# RK05ex.net
KiCad netlist of a schematic drawn in EAGLE
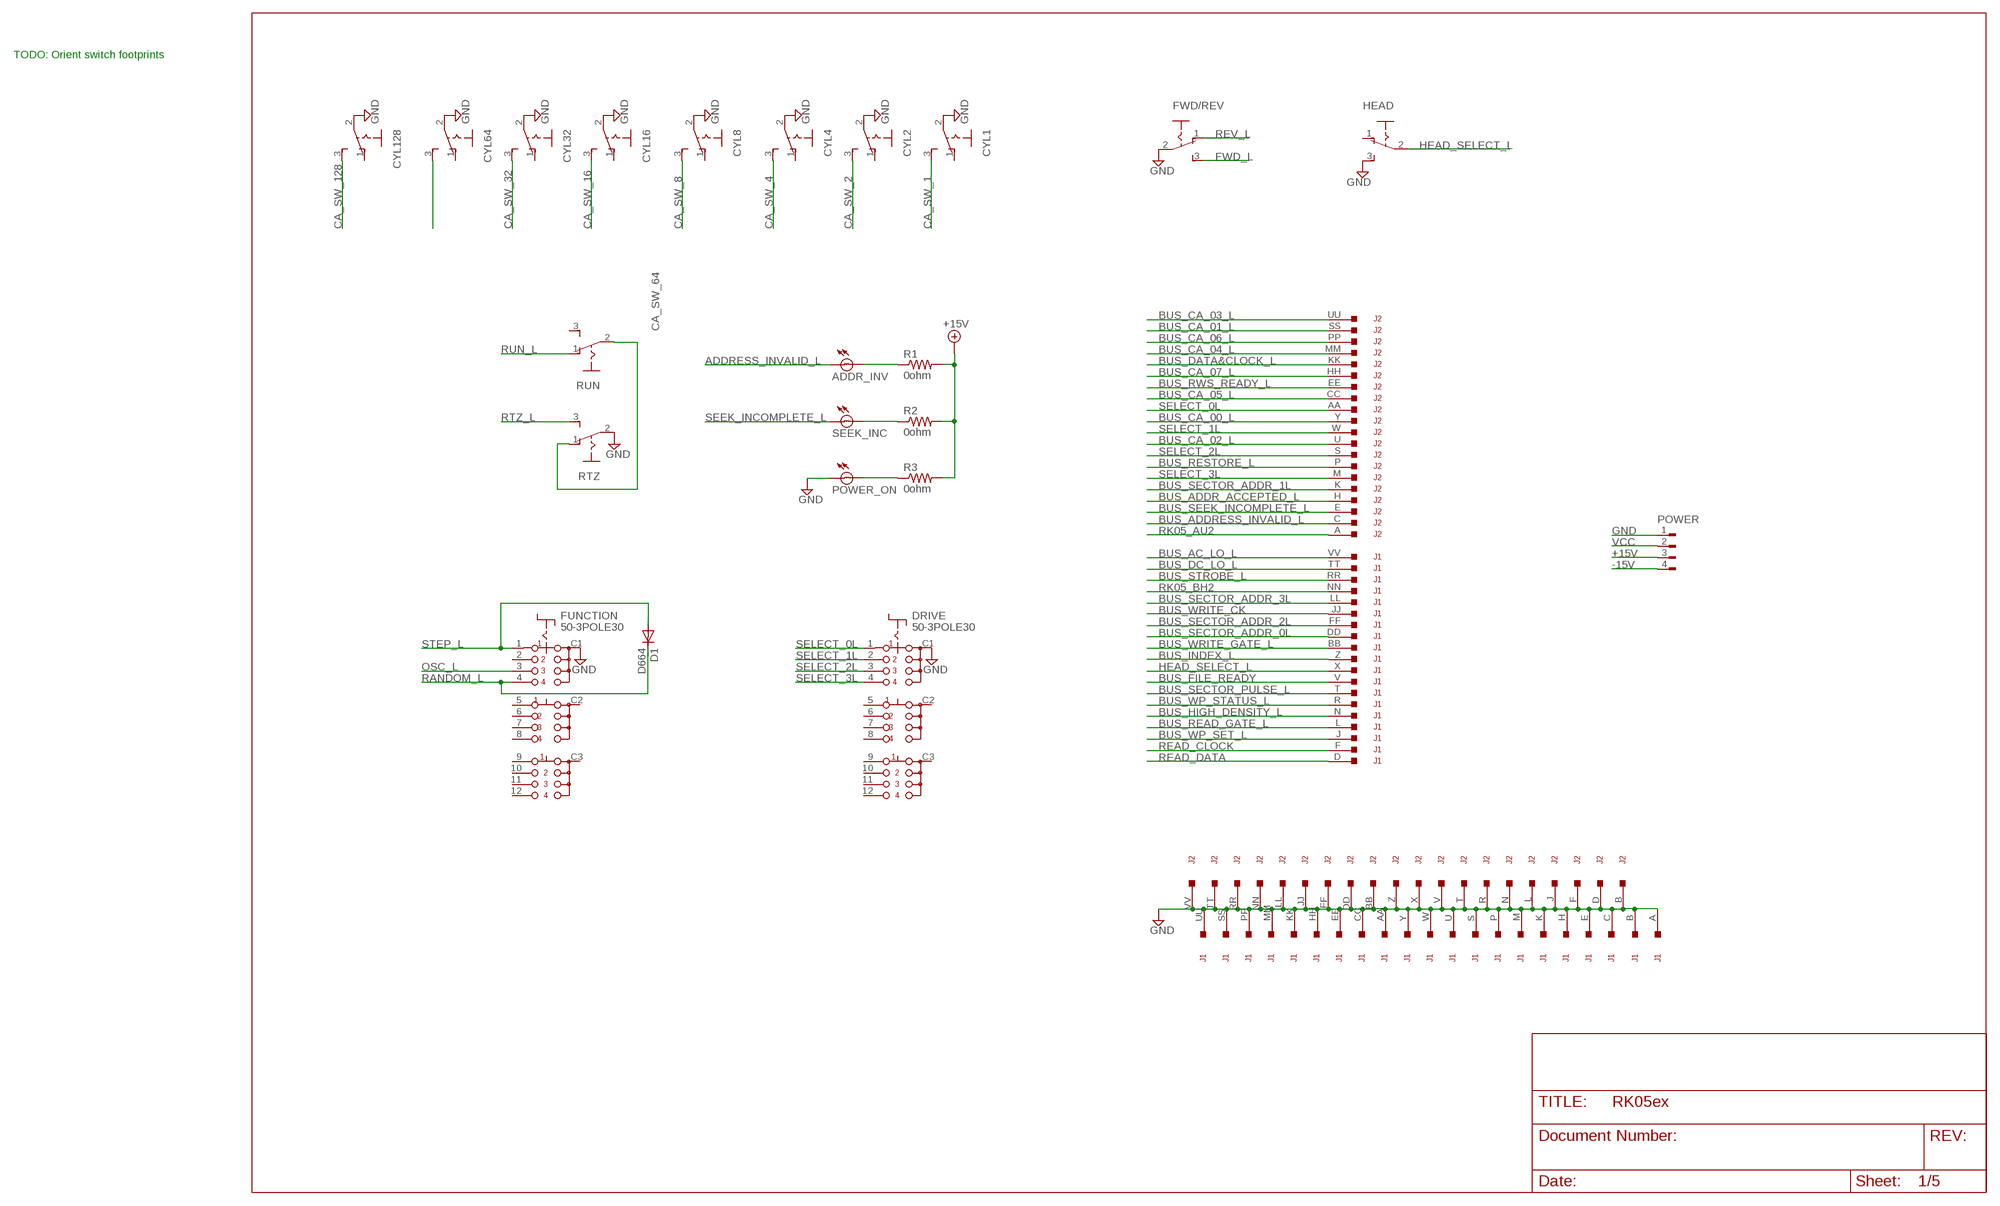
[diagram p0: schematic, sheet 1]
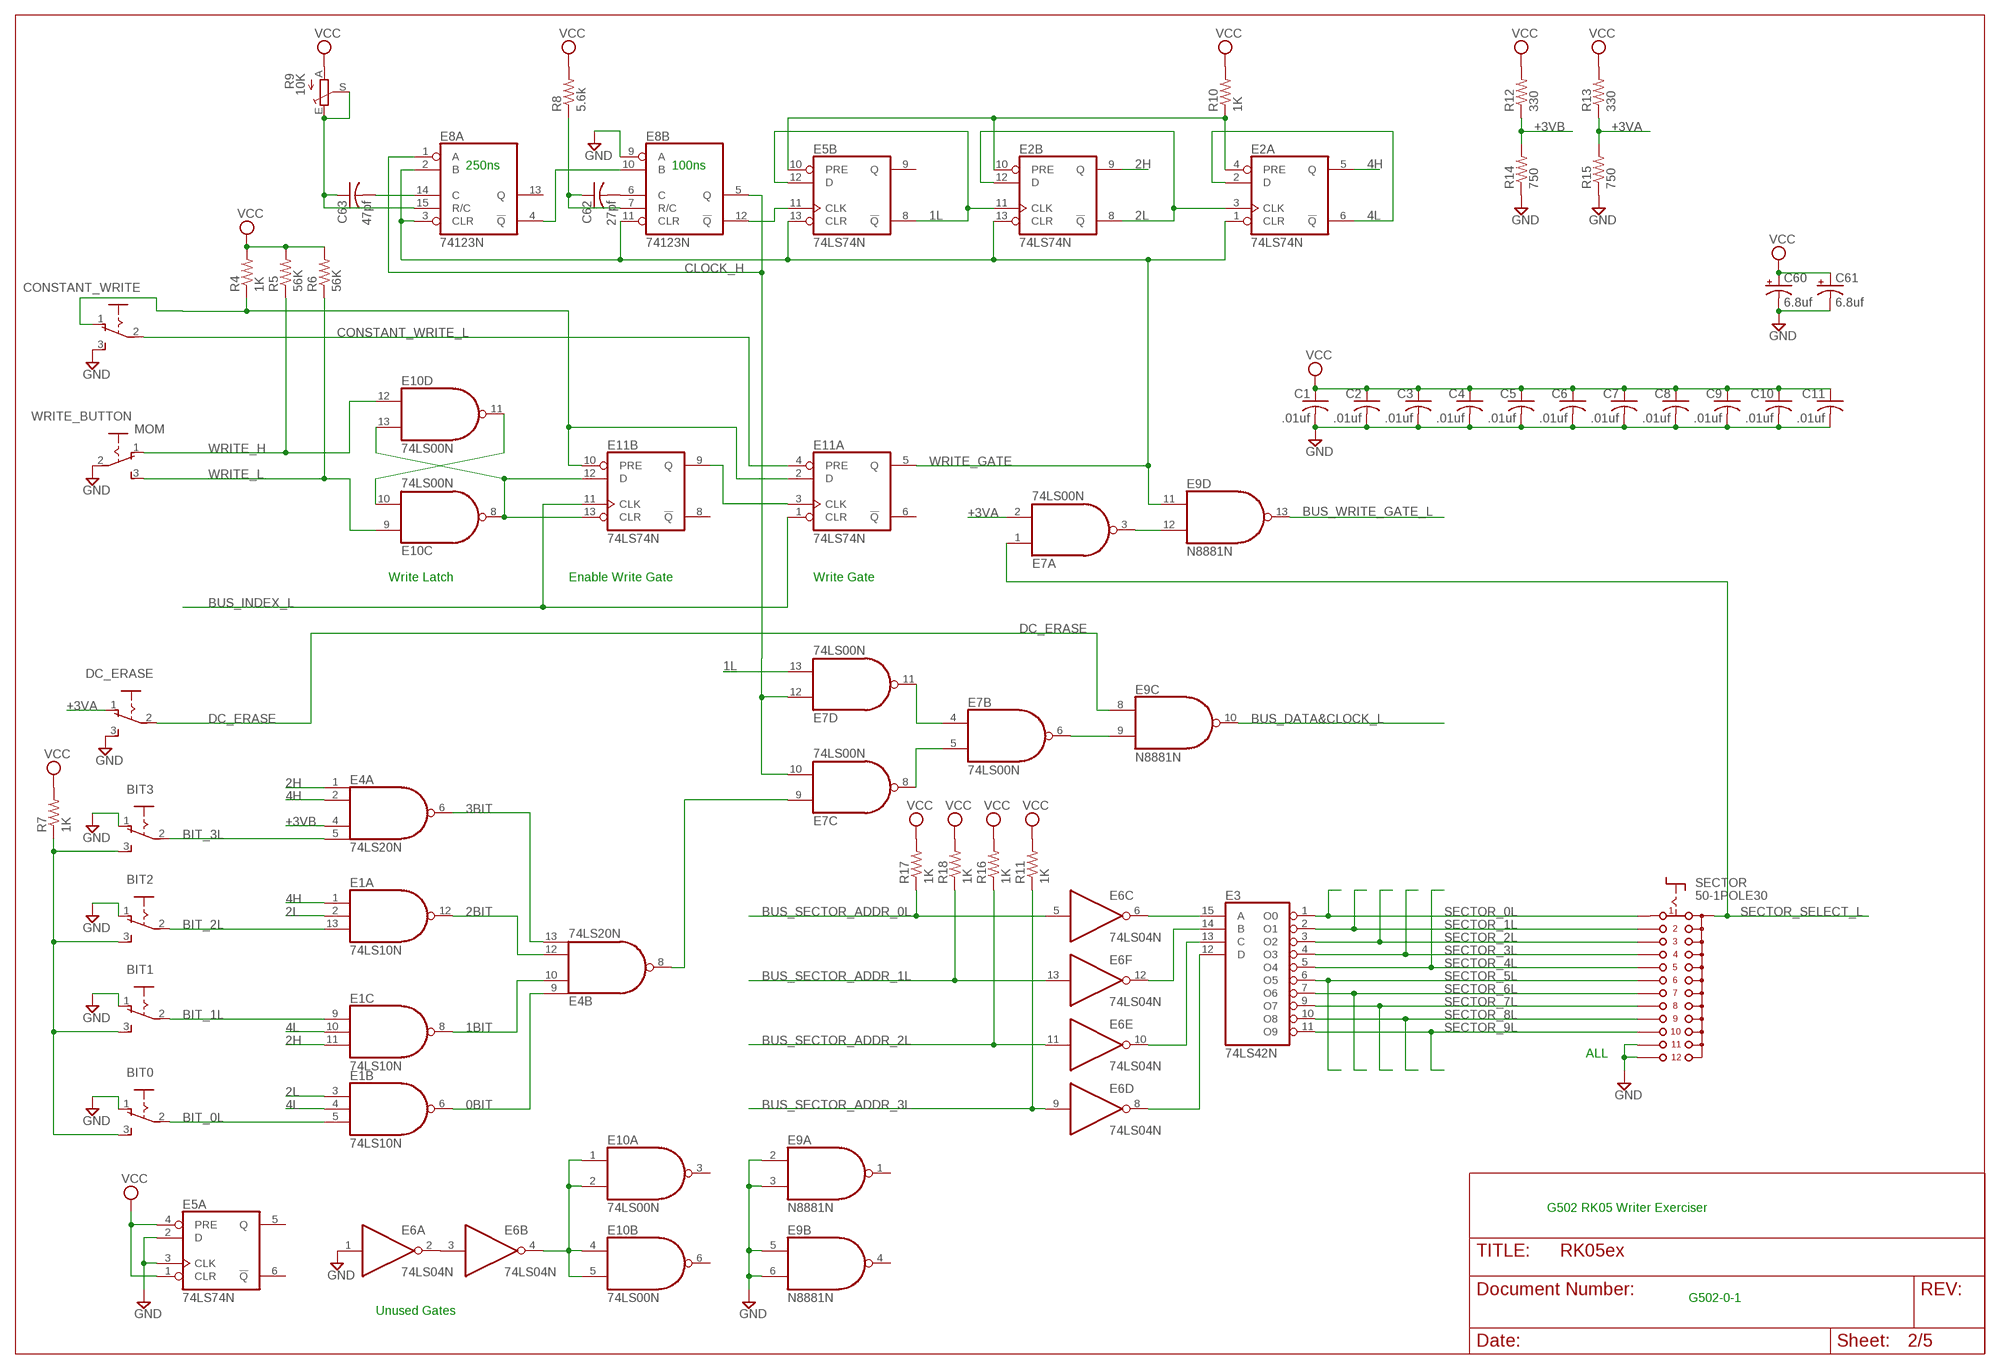
[diagram p1: schematic, sheet 2]
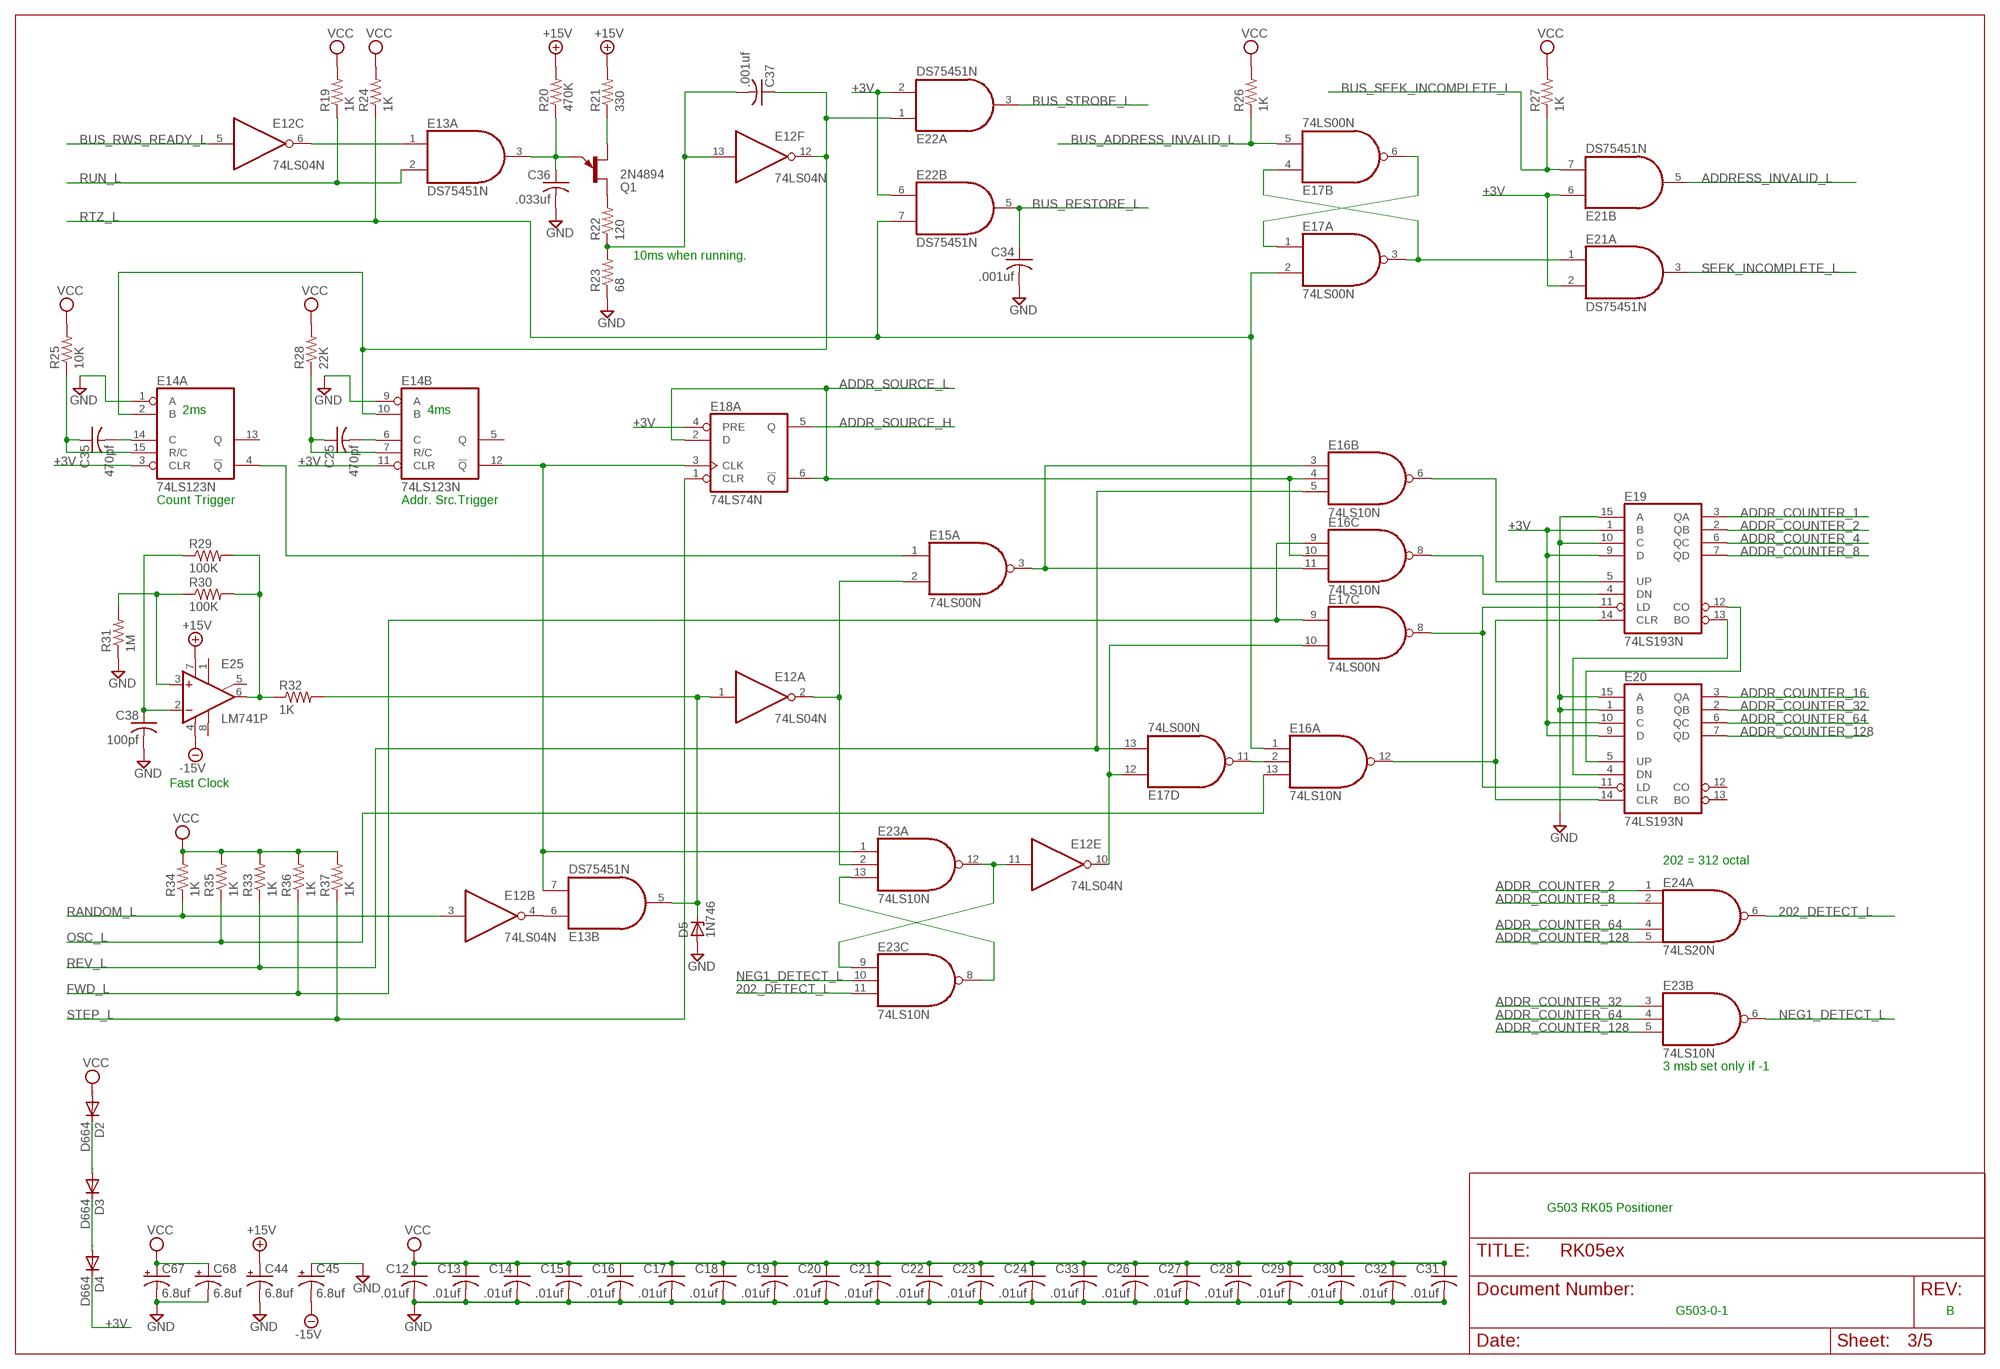
[diagram p2: schematic, sheet 3]
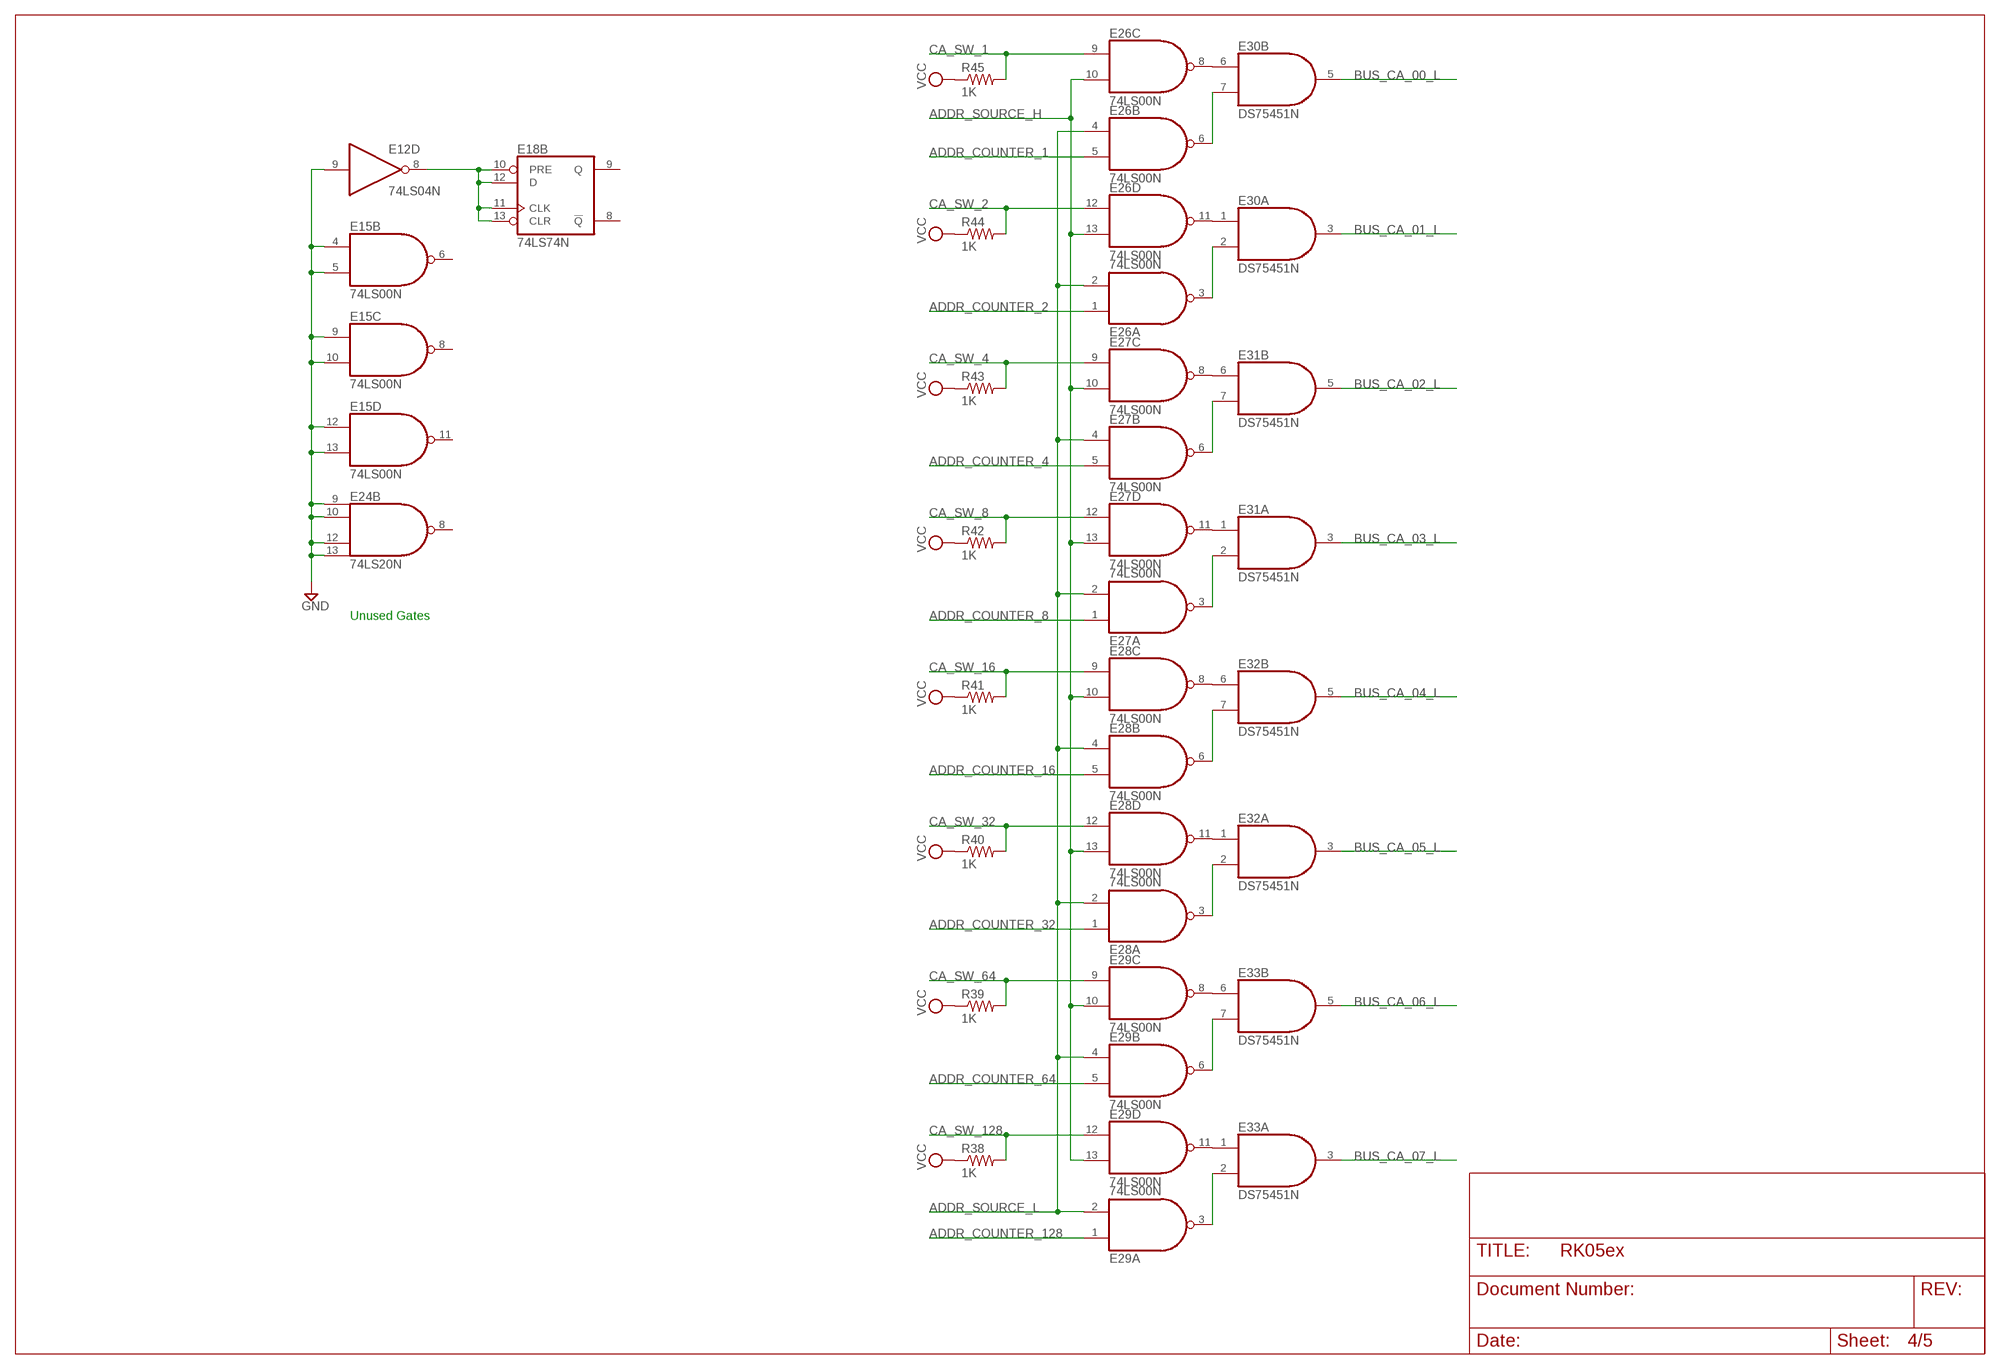
[diagram p3: schematic, sheet 4]
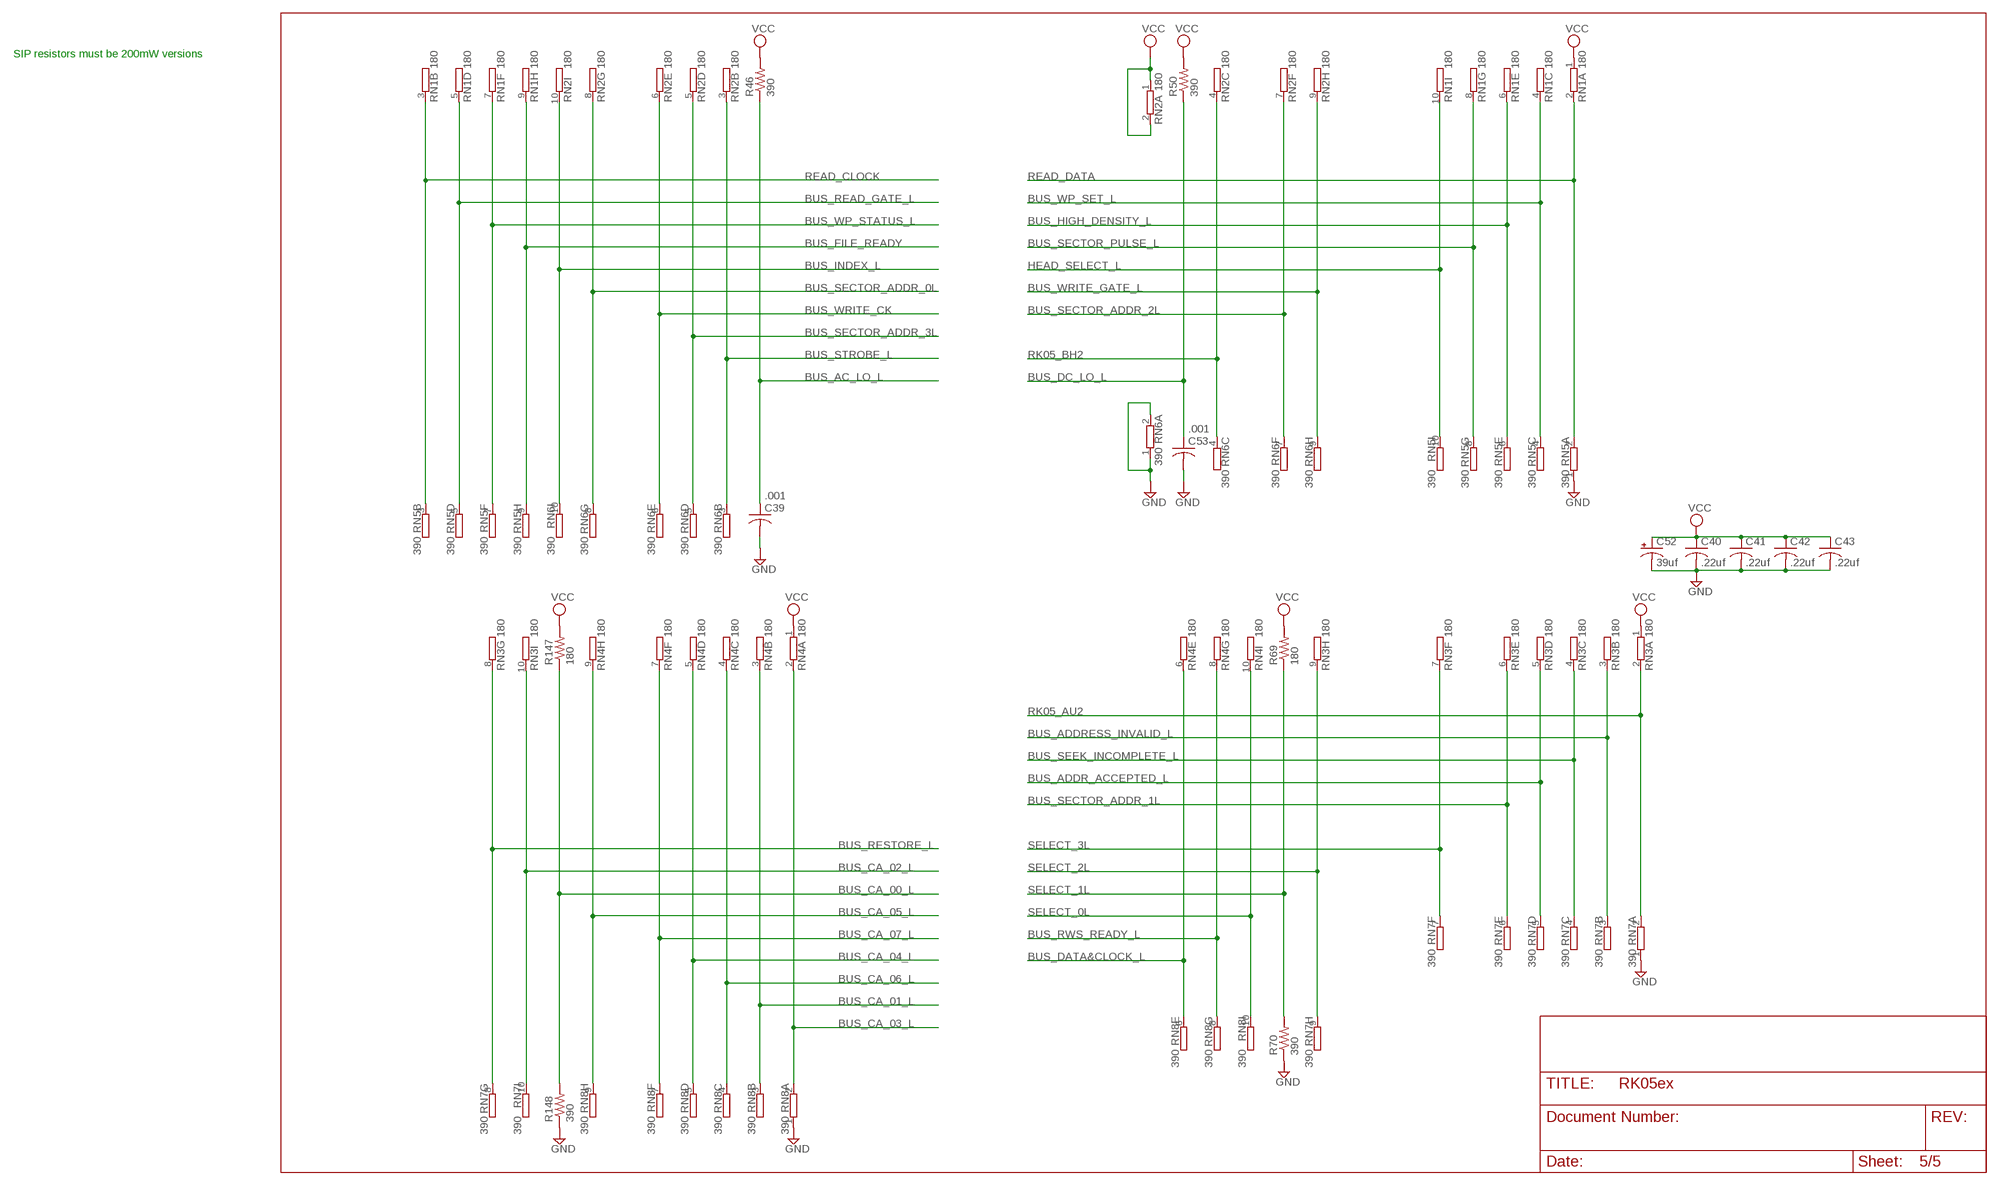
[diagram p4: schematic, sheet 5]

(export (version "E")
  (design (tool "Eeschema 10.0.6"))
  (components
    (comp (ref "C12")
      (value ".01uf")
      (footprint "eagle-import:C075-032X103")
      (libsource (lib "eagle-import") (part "C-US075-032X103"))
    )
    (comp (ref "C13")
      (value ".01uf")
      (footprint "eagle-import:C075-032X103")
      (libsource (lib "eagle-import") (part "C-US075-032X103"))
    )
    (comp (ref "C14")
      (value ".01uf")
      (footprint "eagle-import:C075-032X103")
      (libsource (lib "eagle-import") (part "C-US075-032X103"))
    )
    (comp (ref "C15")
      (value ".01uf")
      (footprint "eagle-import:C075-032X103")
      (libsource (lib "eagle-import") (part "C-US075-032X103"))
    )
    (comp (ref "C16")
      (value ".01uf")
      (footprint "eagle-import:C075-032X103")
      (libsource (lib "eagle-import") (part "C-US075-032X103"))
    )
    (comp (ref "C17")
      (value ".01uf")
      (footprint "eagle-import:C075-032X103")
      (libsource (lib "eagle-import") (part "C-US075-032X103"))
    )
    (comp (ref "C18")
      (value ".01uf")
      (footprint "eagle-import:C075-032X103")
      (libsource (lib "eagle-import") (part "C-US075-032X103"))
    )
    (comp (ref "C19")
      (value ".01uf")
      (footprint "eagle-import:C075-032X103")
      (libsource (lib "eagle-import") (part "C-US075-032X103"))
    )
    (comp (ref "C20")
      (value ".01uf")
      (footprint "eagle-import:C075-032X103")
      (libsource (lib "eagle-import") (part "C-US075-032X103"))
    )
    (comp (ref "C21")
      (value ".01uf")
      (footprint "eagle-import:C075-032X103")
      (libsource (lib "eagle-import") (part "C-US075-032X103"))
    )
    (comp (ref "C22")
      (value ".01uf")
      (footprint "eagle-import:C075-032X103")
      (libsource (lib "eagle-import") (part "C-US075-032X103"))
    )
    (comp (ref "C23")
      (value ".01uf")
      (footprint "eagle-import:C075-032X103")
      (libsource (lib "eagle-import") (part "C-US075-032X103"))
    )
    (comp (ref "C24")
      (value ".01uf")
      (footprint "eagle-import:C075-032X103")
      (libsource (lib "eagle-import") (part "C-US075-032X103"))
    )
    (comp (ref "C25")
      (value "470pf")
      (footprint "eagle-import:C075-032X103")
      (libsource (lib "eagle-import") (part "C-US075-032X103"))
    )
    (comp (ref "C26")
      (value ".01uf")
      (footprint "eagle-import:C075-032X103")
      (libsource (lib "eagle-import") (part "C-US075-032X103"))
    )
    (comp (ref "C27")
      (value ".01uf")
      (footprint "eagle-import:C075-032X103")
      (libsource (lib "eagle-import") (part "C-US075-032X103"))
    )
    (comp (ref "C28")
      (value ".01uf")
      (footprint "eagle-import:C075-032X103")
      (libsource (lib "eagle-import") (part "C-US075-032X103"))
    )
    (comp (ref "C29")
      (value ".01uf")
      (footprint "eagle-import:C075-032X103")
      (libsource (lib "eagle-import") (part "C-US075-032X103"))
    )
    (comp (ref "C30")
      (value ".01uf")
      (footprint "eagle-import:C075-032X103")
      (libsource (lib "eagle-import") (part "C-US075-032X103"))
    )
    (comp (ref "C31")
      (value ".01uf")
      (footprint "eagle-import:C075-032X103")
      (libsource (lib "eagle-import") (part "C-US075-032X103"))
    )
    (comp (ref "C32")
      (value ".01uf")
      (footprint "eagle-import:C075-032X103")
      (libsource (lib "eagle-import") (part "C-US075-032X103"))
    )
    (comp (ref "C33")
      (value ".01uf")
      (footprint "eagle-import:C075-032X103")
      (libsource (lib "eagle-import") (part "C-US075-032X103"))
    )
    (comp (ref "C34")
      (value ".001uf")
      (footprint "eagle-import:C075-032X103")
      (libsource (lib "eagle-import") (part "C-US075-032X103"))
    )
    (comp (ref "C35")
      (value "470pf")
      (footprint "eagle-import:C075-032X103")
      (libsource (lib "eagle-import") (part "C-US075-032X103"))
    )
    (comp (ref "C36")
      (value ".033uf")
      (footprint "eagle-import:C075-032X103")
      (libsource (lib "eagle-import") (part "C-US075-032X103"))
    )
    (comp (ref "C37")
      (value ".001uf")
      (footprint "eagle-import:C075-032X103")
      (libsource (lib "eagle-import") (part "C-US075-032X103"))
    )
    (comp (ref "C38")
      (value "100pf")
      (footprint "eagle-import:C075-032X103")
      (libsource (lib "eagle-import") (part "C-US075-032X103"))
    )
    (comp (ref "C44")
      (value "6.8uf")
      (footprint "eagle-import:E15-5")
      (libsource (lib "eagle-import") (part "CPOL-USE15-5AXIAL"))
    )
    (comp (ref "C45")
      (value "6.8uf")
      (footprint "eagle-import:E15-5")
      (libsource (lib "eagle-import") (part "CPOL-USE15-5AXIAL"))
    )
    (comp (ref "C67")
      (value "6.8uf")
      (footprint "eagle-import:E15-5")
      (libsource (lib "eagle-import") (part "CPOL-USE15-5AXIAL"))
    )
    (comp (ref "C68")
      (value "6.8uf")
      (footprint "eagle-import:E15-5")
      (libsource (lib "eagle-import") (part "CPOL-USE15-5AXIAL"))
    )
    (comp (ref "D2")
      (value "D664")
      (footprint "eagle-import:DO35-10")
      (libsource (lib "eagle-import") (part "1N4148DO35-10"))
    )
    (comp (ref "D3")
      (value "D664")
      (footprint "eagle-import:DO35-10")
      (libsource (lib "eagle-import") (part "1N4148DO35-10"))
    )
    (comp (ref "D4")
      (value "D664")
      (footprint "eagle-import:DO35-10")
      (libsource (lib "eagle-import") (part "1N4148DO35-10"))
    )
    (comp (ref "D5")
      (value "1N746")
      (footprint "eagle-import:DO35Z10")
      (libsource (lib "eagle-import") (part "ZENER-DIODEDO35Z10"))
    )
    (comp (ref "E12")
      (value "74LS04N")
      (footprint "eagle-import:DIL14")
      (libsource (lib "eagle-import") (part "7404NLS"))
    )
    (comp (ref "E13")
      (value "DS75451N")
      (footprint "eagle-import:DIL08")
      (libsource (lib "eagle-import") (part "DS75451N"))
    )
    (comp (ref "E14")
      (value "74LS123N")
      (footprint "eagle-import:DIL16")
      (libsource (lib "eagle-import") (part "74123NLS"))
    )
    (comp (ref "E15")
      (value "74LS00N")
      (footprint "eagle-import:DIL14")
      (libsource (lib "eagle-import") (part "7400NLS"))
    )
    (comp (ref "E16")
      (value "74LS10N")
      (footprint "eagle-import:DIL14")
      (libsource (lib "eagle-import") (part "7410NAS"))
    )
    (comp (ref "E17")
      (value "74LS00N")
      (footprint "eagle-import:DIL14")
      (libsource (lib "eagle-import") (part "7400NLS"))
    )
    (comp (ref "E18")
      (value "74LS74N")
      (footprint "eagle-import:DIL14")
      (libsource (lib "eagle-import") (part "7474NLS"))
    )
    (comp (ref "E19")
      (value "74LS193N")
      (footprint "eagle-import:DIL16")
      (libsource (lib "eagle-import") (part "74193NLS"))
    )
    (comp (ref "E20")
      (value "74LS193N")
      (footprint "eagle-import:DIL16")
      (libsource (lib "eagle-import") (part "74193NLS"))
    )
    (comp (ref "E21")
      (value "DS75451N")
      (footprint "eagle-import:DIL08")
      (libsource (lib "eagle-import") (part "DS75451N"))
    )
    (comp (ref "E22")
      (value "DS75451N")
      (footprint "eagle-import:DIL08")
      (libsource (lib "eagle-import") (part "DS75451N"))
    )
    (comp (ref "E23")
      (value "74LS10N")
      (footprint "eagle-import:DIL14")
      (libsource (lib "eagle-import") (part "7410NAS"))
    )
    (comp (ref "E24")
      (value "74LS20N")
      (footprint "eagle-import:DIL14")
      (libsource (lib "eagle-import") (part "7420NLS"))
    )
    (comp (ref "E25")
      (value "LM741P")
      (footprint "eagle-import:DIL08")
      (libsource (lib "eagle-import") (part "741PLM"))
    )
    (comp (ref "Q1")
      (value "2N4894")
      (footprint "eagle-import:TO92E")
      (libsource (lib "eagle-import") (part "2N4870"))
    )
    (comp (ref "R19")
      (value "1K")
      (footprint "eagle-import:0207_10")
      (libsource (lib "eagle-import") (part "R-US_0207/10"))
    )
    (comp (ref "R20")
      (value "470K")
      (footprint "eagle-import:0207_10")
      (libsource (lib "eagle-import") (part "R-US_0207/10"))
    )
    (comp (ref "R21")
      (value "330")
      (footprint "eagle-import:0207_10")
      (libsource (lib "eagle-import") (part "R-US_0207/10"))
    )
    (comp (ref "R22")
      (value "120")
      (footprint "eagle-import:0207_10")
      (libsource (lib "eagle-import") (part "R-US_0207/10"))
    )
    (comp (ref "R23")
      (value "68")
      (footprint "eagle-import:0207_10")
      (libsource (lib "eagle-import") (part "R-US_0207/10"))
    )
    (comp (ref "R24")
      (value "1K")
      (footprint "eagle-import:0207_10")
      (libsource (lib "eagle-import") (part "R-US_0207/10"))
    )
    (comp (ref "R25")
      (value "10K")
      (footprint "eagle-import:0207_10")
      (libsource (lib "eagle-import") (part "R-US_0207/10"))
    )
    (comp (ref "R26")
      (value "1K")
      (footprint "eagle-import:0207_10")
      (libsource (lib "eagle-import") (part "R-US_0207/10"))
    )
    (comp (ref "R27")
      (value "1K")
      (footprint "eagle-import:0207_10")
      (libsource (lib "eagle-import") (part "R-US_0207/10"))
    )
    (comp (ref "R28")
      (value "22K")
      (footprint "eagle-import:0207_10")
      (libsource (lib "eagle-import") (part "R-US_0207/10"))
    )
    (comp (ref "R29")
      (value "100K")
      (footprint "eagle-import:0207_10")
      (libsource (lib "eagle-import") (part "R-US_0207/10"))
    )
    (comp (ref "R30")
      (value "100K")
      (footprint "eagle-import:0207_10")
      (libsource (lib "eagle-import") (part "R-US_0207/10"))
    )
    (comp (ref "R31")
      (value "1M")
      (footprint "eagle-import:0207_10")
      (libsource (lib "eagle-import") (part "R-US_0207/10"))
    )
    (comp (ref "R32")
      (value "1K")
      (footprint "eagle-import:0207_10")
      (libsource (lib "eagle-import") (part "R-US_0207/10"))
    )
    (comp (ref "R33")
      (value "1K")
      (footprint "eagle-import:0207_10")
      (libsource (lib "eagle-import") (part "R-US_0207/10"))
    )
    (comp (ref "R34")
      (value "1K")
      (footprint "eagle-import:0207_10")
      (libsource (lib "eagle-import") (part "R-US_0207/10"))
    )
    (comp (ref "R35")
      (value "1K")
      (footprint "eagle-import:0207_10")
      (libsource (lib "eagle-import") (part "R-US_0207/10"))
    )
    (comp (ref "R36")
      (value "1K")
      (footprint "eagle-import:0207_10")
      (libsource (lib "eagle-import") (part "R-US_0207/10"))
    )
    (comp (ref "R37")
      (value "1K")
      (footprint "eagle-import:0207_10")
      (libsource (lib "eagle-import") (part "R-US_0207/10"))
    )
    (comp (ref "E26")
      (value "74LS00N")
      (footprint "eagle-import:DIL14")
      (libsource (lib "eagle-import") (part "7400NLS"))
    )
    (comp (ref "E27")
      (value "74LS00N")
      (footprint "eagle-import:DIL14")
      (libsource (lib "eagle-import") (part "7400NLS"))
    )
    (comp (ref "E28")
      (value "74LS00N")
      (footprint "eagle-import:DIL14")
      (libsource (lib "eagle-import") (part "7400NLS"))
    )
    (comp (ref "E29")
      (value "74LS00N")
      (footprint "eagle-import:DIL14")
      (libsource (lib "eagle-import") (part "7400NLS"))
    )
    (comp (ref "E30")
      (value "DS75451N")
      (footprint "eagle-import:DIL08")
      (libsource (lib "eagle-import") (part "DS75451N"))
    )
    (comp (ref "E31")
      (value "DS75451N")
      (footprint "eagle-import:DIL08")
      (libsource (lib "eagle-import") (part "DS75451N"))
    )
    (comp (ref "E32")
      (value "DS75451N")
      (footprint "eagle-import:DIL08")
      (libsource (lib "eagle-import") (part "DS75451N"))
    )
    (comp (ref "E33")
      (value "DS75451N")
      (footprint "eagle-import:DIL08")
      (libsource (lib "eagle-import") (part "DS75451N"))
    )
    (comp (ref "R38")
      (value "1K")
      (footprint "eagle-import:0207_10")
      (libsource (lib "eagle-import") (part "R-US_0207/10"))
    )
    (comp (ref "R39")
      (value "1K")
      (footprint "eagle-import:0207_10")
      (libsource (lib "eagle-import") (part "R-US_0207/10"))
    )
    (comp (ref "R40")
      (value "1K")
      (footprint "eagle-import:0207_10")
      (libsource (lib "eagle-import") (part "R-US_0207/10"))
    )
    (comp (ref "R41")
      (value "1K")
      (footprint "eagle-import:0207_10")
      (libsource (lib "eagle-import") (part "R-US_0207/10"))
    )
    (comp (ref "R42")
      (value "1K")
      (footprint "eagle-import:0207_10")
      (libsource (lib "eagle-import") (part "R-US_0207/10"))
    )
    (comp (ref "R43")
      (value "1K")
      (footprint "eagle-import:0207_10")
      (libsource (lib "eagle-import") (part "R-US_0207/10"))
    )
    (comp (ref "R44")
      (value "1K")
      (footprint "eagle-import:0207_10")
      (libsource (lib "eagle-import") (part "R-US_0207/10"))
    )
    (comp (ref "R45")
      (value "1K")
      (footprint "eagle-import:0207_10")
      (libsource (lib "eagle-import") (part "R-US_0207/10"))
    )
    (comp (ref "C39")
      (value ".001")
      (footprint "eagle-import:C050-025X075")
      (libsource (lib "eagle-import") (part "C-US050-025X075"))
    )
    (comp (ref "C40")
      (value ".22uf")
      (footprint "eagle-import:C050-025X075")
      (libsource (lib "eagle-import") (part "C-US050-025X075"))
    )
    (comp (ref "C41")
      (value ".22uf")
      (footprint "eagle-import:C050-025X075")
      (libsource (lib "eagle-import") (part "C-US050-025X075"))
    )
    (comp (ref "C42")
      (value ".22uf")
      (footprint "eagle-import:C050-025X075")
      (libsource (lib "eagle-import") (part "C-US050-025X075"))
    )
    (comp (ref "C43")
      (value ".22uf")
      (footprint "eagle-import:C050-025X075")
      (libsource (lib "eagle-import") (part "C-US050-025X075"))
    )
    (comp (ref "C52")
      (value "39uf")
      (footprint "eagle-import:E15-5")
      (libsource (lib "eagle-import") (part "CPOL-USE15-5AXIAL"))
    )
    (comp (ref "C53")
      (value ".001")
      (footprint "eagle-import:C050-025X075")
      (libsource (lib "eagle-import") (part "C-US050-025X075"))
    )
    (comp (ref "R46")
      (value "390")
      (footprint "eagle-import:0207_10")
      (libsource (lib "eagle-import") (part "R-US_0207/10"))
    )
    (comp (ref "R50")
      (value "390")
      (footprint "eagle-import:0207_10")
      (libsource (lib "eagle-import") (part "R-US_0207/10"))
    )
    (comp (ref "R69")
      (value "180")
      (footprint "eagle-import:0207_10")
      (libsource (lib "eagle-import") (part "R-US_0207/10"))
    )
    (comp (ref "R70")
      (value "390")
      (footprint "eagle-import:0207_10")
      (libsource (lib "eagle-import") (part "R-US_0207/10"))
    )
    (comp (ref "R147")
      (value "180")
      (footprint "eagle-import:0207_10")
      (libsource (lib "eagle-import") (part "R-US_0207/10"))
    )
    (comp (ref "R148")
      (value "390")
      (footprint "eagle-import:0207_10")
      (libsource (lib "eagle-import") (part "R-US_0207/10"))
    )
    (comp (ref "RN1")
      (value "180")
      (footprint "eagle-import:SIL10")
      (libsource (lib "eagle-import") (part "GE09R"))
    )
    (comp (ref "RN2")
      (value "180")
      (footprint "eagle-import:SIL10")
      (libsource (lib "eagle-import") (part "GE09R"))
    )
    (comp (ref "RN3")
      (value "180")
      (footprint "eagle-import:SIL10")
      (libsource (lib "eagle-import") (part "GE09R"))
    )
    (comp (ref "RN4")
      (value "180")
      (footprint "eagle-import:SIL10")
      (libsource (lib "eagle-import") (part "GE09R"))
    )
    (comp (ref "RN5")
      (value "390")
      (footprint "eagle-import:SIL10")
      (libsource (lib "eagle-import") (part "GE09R"))
    )
    (comp (ref "RN6")
      (value "390")
      (footprint "eagle-import:SIL10")
      (libsource (lib "eagle-import") (part "GE09R"))
    )
    (comp (ref "RN7")
      (value "390")
      (footprint "eagle-import:SIL10")
      (libsource (lib "eagle-import") (part "GE09R"))
    )
    (comp (ref "RN8")
      (value "390")
      (footprint "eagle-import:SIL10")
      (libsource (lib "eagle-import") (part "GE09R"))
    )
    (comp (ref "BIT0")
      (value "255SB")
      (footprint "eagle-import:255SB")
      (libsource (lib "eagle-import") (part "255SB"))
    )
    (comp (ref "BIT1")
      (value "255SB")
      (footprint "eagle-import:255SB")
      (libsource (lib "eagle-import") (part "255SB"))
    )
    (comp (ref "BIT2")
      (value "255SB")
      (footprint "eagle-import:255SB")
      (libsource (lib "eagle-import") (part "255SB"))
    )
    (comp (ref "BIT3")
      (value "255SB")
      (footprint "eagle-import:255SB")
      (libsource (lib "eagle-import") (part "255SB"))
    )
    (comp (ref "C1")
      (value ".01uf")
      (footprint "eagle-import:C075-032X103")
      (libsource (lib "eagle-import") (part "C-US075-032X103"))
    )
    (comp (ref "C2")
      (value ".01uf")
      (footprint "eagle-import:C075-032X103")
      (libsource (lib "eagle-import") (part "C-US075-032X103"))
    )
    (comp (ref "C3")
      (value ".01uf")
      (footprint "eagle-import:C075-032X103")
      (libsource (lib "eagle-import") (part "C-US075-032X103"))
    )
    (comp (ref "C4")
      (value ".01uf")
      (footprint "eagle-import:C075-032X103")
      (libsource (lib "eagle-import") (part "C-US075-032X103"))
    )
    (comp (ref "C5")
      (value ".01uf")
      (footprint "eagle-import:C075-032X103")
      (libsource (lib "eagle-import") (part "C-US075-032X103"))
    )
    (comp (ref "C6")
      (value ".01uf")
      (footprint "eagle-import:C075-032X103")
      (libsource (lib "eagle-import") (part "C-US075-032X103"))
    )
    (comp (ref "C7")
      (value ".01uf")
      (footprint "eagle-import:C075-032X103")
      (libsource (lib "eagle-import") (part "C-US075-032X103"))
    )
    (comp (ref "C8")
      (value ".01uf")
      (footprint "eagle-import:C075-032X103")
      (libsource (lib "eagle-import") (part "C-US075-032X103"))
    )
    (comp (ref "C9")
      (value ".01uf")
      (footprint "eagle-import:C075-032X103")
      (libsource (lib "eagle-import") (part "C-US075-032X103"))
    )
    (comp (ref "C10")
      (value ".01uf")
      (footprint "eagle-import:C075-032X103")
      (libsource (lib "eagle-import") (part "C-US075-032X103"))
    )
    (comp (ref "C11")
      (value ".01uf")
      (footprint "eagle-import:C075-032X103")
      (libsource (lib "eagle-import") (part "C-US075-032X103"))
    )
    (comp (ref "C60")
      (value "6.8uf")
      (footprint "eagle-import:E15-5")
      (libsource (lib "eagle-import") (part "CPOL-USE15-5AXIAL"))
    )
    (comp (ref "C61")
      (value "6.8uf")
      (footprint "eagle-import:E15-5")
      (libsource (lib "eagle-import") (part "CPOL-USE15-5AXIAL"))
    )
    (comp (ref "C62")
      (value "27pf")
      (footprint "eagle-import:C075-032X103")
      (libsource (lib "eagle-import") (part "C-US075-032X103"))
    )
    (comp (ref "C63")
      (value "47pf")
      (footprint "eagle-import:C075-032X103")
      (libsource (lib "eagle-import") (part "C-US075-032X103"))
    )
    (comp (ref "CONSTANT_WRITE")
      (value "255SB")
      (footprint "eagle-import:255SB")
      (libsource (lib "eagle-import") (part "255SB"))
    )
    (comp (ref "DC_ERASE")
      (value "255SB")
      (footprint "eagle-import:255SB")
      (libsource (lib "eagle-import") (part "255SB"))
    )
    (comp (ref "E1")
      (value "74LS10N")
      (footprint "eagle-import:DIL14")
      (libsource (lib "eagle-import") (part "7410NLS"))
    )
    (comp (ref "E2")
      (value "74LS74N")
      (footprint "eagle-import:DIL14")
      (libsource (lib "eagle-import") (part "7474NLS"))
    )
    (comp (ref "E3")
      (value "74LS42N")
      (footprint "eagle-import:DIL16")
      (libsource (lib "eagle-import") (part "7442NLS"))
    )
    (comp (ref "E4")
      (value "74LS20N")
      (footprint "eagle-import:DIL14")
      (libsource (lib "eagle-import") (part "7420NLS"))
    )
    (comp (ref "E5")
      (value "74LS74N")
      (footprint "eagle-import:DIL14")
      (libsource (lib "eagle-import") (part "7474NLS"))
    )
    (comp (ref "E6")
      (value "74LS04N")
      (footprint "eagle-import:DIL14")
      (libsource (lib "eagle-import") (part "7404NLS"))
    )
    (comp (ref "E7")
      (value "74LS00N")
      (footprint "eagle-import:DIL14")
      (libsource (lib "eagle-import") (part "7400NLS"))
    )
    (comp (ref "E8")
      (value "74123N")
      (footprint "eagle-import:DIL16")
      (libsource (lib "eagle-import") (part "74123NLS"))
    )
    (comp (ref "E9")
      (value "N8881N")
      (footprint "eagle-import:DIL14")
      (libsource (lib "eagle-import") (part "N8881N"))
    )
    (comp (ref "E10")
      (value "74LS00N")
      (footprint "eagle-import:DIL14")
      (libsource (lib "eagle-import") (part "7400NLS"))
    )
    (comp (ref "E11")
      (value "74LS74N")
      (footprint "eagle-import:DIL14")
      (libsource (lib "eagle-import") (part "7474NLS"))
    )
    (comp (ref "R4")
      (value "1K")
      (footprint "eagle-import:0207_10")
      (libsource (lib "eagle-import") (part "R-US_0207/10"))
    )
    (comp (ref "R5")
      (value "56K")
      (footprint "eagle-import:0207_10")
      (libsource (lib "eagle-import") (part "R-US_0207/10"))
    )
    (comp (ref "R6")
      (value "56K")
      (footprint "eagle-import:0207_10")
      (libsource (lib "eagle-import") (part "R-US_0207/10"))
    )
    (comp (ref "R7")
      (value "1K")
      (footprint "eagle-import:0207_10")
      (libsource (lib "eagle-import") (part "R-US_0207/10"))
    )
    (comp (ref "R8")
      (value "5.6k")
      (footprint "eagle-import:0207_10")
      (libsource (lib "eagle-import") (part "R-US_0207/10"))
    )
    (comp (ref "R9")
      (value "10K")
      (footprint "eagle-import:SP19L")
      (libsource (lib "eagle-import") (part "TRIM_EU-B90P"))
    )
    (comp (ref "R10")
      (value "1K")
      (footprint "eagle-import:0207_10")
      (libsource (lib "eagle-import") (part "R-US_0207/10"))
    )
    (comp (ref "R11")
      (value "1K")
      (footprint "eagle-import:0207_10")
      (libsource (lib "eagle-import") (part "R-US_0207/10"))
    )
    (comp (ref "R12")
      (value "330")
      (footprint "eagle-import:0207_10")
      (libsource (lib "eagle-import") (part "R-US_0207/10"))
    )
    (comp (ref "R13")
      (value "330")
      (footprint "eagle-import:0207_10")
      (libsource (lib "eagle-import") (part "R-US_0207/10"))
    )
    (comp (ref "R14")
      (value "750")
      (footprint "eagle-import:0207_10")
      (libsource (lib "eagle-import") (part "R-US_0207/10"))
    )
    (comp (ref "R15")
      (value "750")
      (footprint "eagle-import:0207_10")
      (libsource (lib "eagle-import") (part "R-US_0207/10"))
    )
    (comp (ref "R16")
      (value "1K")
      (footprint "eagle-import:0207_10")
      (libsource (lib "eagle-import") (part "R-US_0207/10"))
    )
    (comp (ref "R17")
      (value "1K")
      (footprint "eagle-import:0207_10")
      (libsource (lib "eagle-import") (part "R-US_0207/10"))
    )
    (comp (ref "R18")
      (value "1K")
      (footprint "eagle-import:0207_10")
      (libsource (lib "eagle-import") (part "R-US_0207/10"))
    )
    (comp (ref "SECTOR")
      (value "50-1POLE30")
      (footprint "eagle-import:50-1POLE30")
      (libsource (lib "eagle-import") (part "50-1POLE30"))
    )
    (comp (ref "WRITE_BUTTON")
      (value "MOM")
      (footprint "eagle-import:255SB")
      (libsource (lib "eagle-import") (part "255SB"))
    )
    (comp (ref "ADDR_INV")
      (value "BULB")
      (footprint "eagle-import:BULB")
      (libsource (lib "eagle-import") (part "BULB"))
    )
    (comp (ref "CYL1")
      (value "255SB")
      (footprint "eagle-import:255SB")
      (libsource (lib "eagle-import") (part "255SB"))
    )
    (comp (ref "CYL2")
      (value "255SB")
      (footprint "eagle-import:255SB")
      (libsource (lib "eagle-import") (part "255SB"))
    )
    (comp (ref "CYL4")
      (value "255SB")
      (footprint "eagle-import:255SB")
      (libsource (lib "eagle-import") (part "255SB"))
    )
    (comp (ref "CYL8")
      (value "255SB")
      (footprint "eagle-import:255SB")
      (libsource (lib "eagle-import") (part "255SB"))
    )
    (comp (ref "CYL16")
      (value "255SB")
      (footprint "eagle-import:255SB")
      (libsource (lib "eagle-import") (part "255SB"))
    )
    (comp (ref "CYL32")
      (value "255SB")
      (footprint "eagle-import:255SB")
      (libsource (lib "eagle-import") (part "255SB"))
    )
    (comp (ref "CYL64")
      (value "255SB")
      (footprint "eagle-import:255SB")
      (libsource (lib "eagle-import") (part "255SB"))
    )
    (comp (ref "CYL128")
      (value "255SB")
      (footprint "eagle-import:255SB")
      (libsource (lib "eagle-import") (part "255SB"))
    )
    (comp (ref "D1")
      (value "D664")
      (footprint "eagle-import:DO35-10")
      (libsource (lib "eagle-import") (part "1N4148DO35-10"))
    )
    (comp (ref "DRIVE")
      (value "50-3POLE30")
      (footprint "eagle-import:50-3POLE30")
      (libsource (lib "eagle-import") (part "50-3POLE30"))
    )
    (comp (ref "FUNCTION")
      (value "50-3POLE30")
      (footprint "eagle-import:50-3POLE30")
      (libsource (lib "eagle-import") (part "50-3POLE30"))
    )
    (comp (ref "FWD/REV")
      (value "255SB")
      (footprint "eagle-import:255SB")
      (libsource (lib "eagle-import") (part "255SB"))
    )
    (comp (ref "HEAD")
      (value "255SB")
      (footprint "eagle-import:255SB")
      (libsource (lib "eagle-import") (part "255SB"))
    )
    (comp (ref "J1")
      (value "DEC40PINSV")
      (footprint "eagle-import:DEC40PINV")
      (libsource (lib "eagle-import") (part "DEC40PINSV"))
    )
    (comp (ref "J2")
      (value "DEC40PINSV")
      (footprint "eagle-import:DEC40PINV")
      (libsource (lib "eagle-import") (part "DEC40PINSV"))
    )
    (comp (ref "POWER")
      (value "FLOPPY-4")
      (footprint "eagle-import:FLOPPY-4")
      (libsource (lib "eagle-import") (part "FLOPPY-4"))
    )
    (comp (ref "POWER_ON")
      (value "BULB")
      (footprint "eagle-import:BULB")
      (libsource (lib "eagle-import") (part "BULB"))
    )
    (comp (ref "R1")
      (value "0ohm")
      (footprint "eagle-import:0207_10")
      (libsource (lib "eagle-import") (part "R-US_0207/10"))
    )
    (comp (ref "R2")
      (value "0ohm")
      (footprint "eagle-import:0207_10")
      (libsource (lib "eagle-import") (part "R-US_0207/10"))
    )
    (comp (ref "R3")
      (value "0ohm")
      (footprint "eagle-import:0207_10")
      (libsource (lib "eagle-import") (part "R-US_0207/10"))
    )
    (comp (ref "RTZ")
      (value "255SB")
      (footprint "eagle-import:255SB")
      (libsource (lib "eagle-import") (part "255SB"))
    )
    (comp (ref "RUN")
      (value "255SB")
      (footprint "eagle-import:255SB")
      (libsource (lib "eagle-import") (part "255SB"))
    )
    (comp (ref "SEEK_INC")
      (value "BULB")
      (footprint "eagle-import:BULB")
      (libsource (lib "eagle-import") (part "BULB"))
    )
  )
  (nets
    (net (code "1") (name "+3V") (class "Default")
      (node (ref "D4") (pin "C") (pinfunction "C_C") (pintype "passive"))
      (node (ref "E14") (pin "11") (pinfunction "CLR_11") (pintype "input"))
      (node (ref "E14") (pin "3") (pinfunction "CLR_3") (pintype "input"))
      (node (ref "E18") (pin "4") (pinfunction "PRE_4") (pintype "input"))
      (node (ref "E19") (pin "1") (pinfunction "B_1") (pintype "input"))
      (node (ref "E19") (pin "9") (pinfunction "D_9") (pintype "input"))
      (node (ref "E20") (pin "10") (pinfunction "C_10") (pintype "input"))
      (node (ref "E20") (pin "9") (pinfunction "D_9") (pintype "input"))
      (node (ref "E21") (pin "2") (pinfunction "I1_2") (pintype "input"))
      (node (ref "E21") (pin "6") (pinfunction "I0_6") (pintype "input"))
      (node (ref "E22") (pin "2") (pinfunction "I1_2") (pintype "input"))
      (node (ref "E22") (pin "6") (pinfunction "I0_6") (pintype "input"))
    )
    (net (code "2") (name "+3VA") (class "Default")
      (node (ref "DC_ERASE") (pin "1") (pinfunction "O_1") (pintype "passive"))
      (node (ref "E7") (pin "2") (pinfunction "I1_2") (pintype "input"))
      (node (ref "R13") (pin "1") (pinfunction "1_1") (pintype "passive"))
      (node (ref "R15") (pin "2") (pinfunction "2_2") (pintype "passive"))
    )
    (net (code "3") (name "+3VB") (class "Default")
      (node (ref "E4") (pin "4") (pinfunction "I2_4") (pintype "input"))
      (node (ref "R12") (pin "1") (pinfunction "1_1") (pintype "passive"))
      (node (ref "R14") (pin "2") (pinfunction "2_2") (pintype "passive"))
    )
    (net (code "4") (name "+15V") (class "Default")
      (node (ref "C44") (pin "+") (pinfunction "+_+") (pintype "passive"))
      (node (ref "E25") (pin "7") (pinfunction "V+_7") (pintype "power_in"))
      (node (ref "POWER") (pin "3") (pinfunction "3_3") (pintype "passive"))
      (node (ref "R1") (pin "2") (pinfunction "2_2") (pintype "passive"))
      (node (ref "R2") (pin "2") (pinfunction "2_2") (pintype "passive"))
      (node (ref "R20") (pin "2") (pinfunction "2_2") (pintype "passive"))
      (node (ref "R21") (pin "2") (pinfunction "2_2") (pintype "passive"))
      (node (ref "R3") (pin "2") (pinfunction "2_2") (pintype "passive"))
    )
    (net (code "5") (name "-15V") (class "Default")
      (node (ref "C45") (pin "-") (pinfunction "-_-") (pintype "passive"))
      (node (ref "E25") (pin "4") (pinfunction "V-_4") (pintype "power_in"))
      (node (ref "POWER") (pin "4") (pinfunction "4_4") (pintype "passive"))
    )
    (net (code "6") (name "0BIT") (class "Default")
      (node (ref "E1") (pin "6") (pinfunction "O_6") (pintype "output"))
      (node (ref "E4") (pin "9") (pinfunction "I0_9") (pintype "input"))
    )
    (net (code "7") (name "1BIT") (class "Default")
      (node (ref "E1") (pin "8") (pinfunction "O_8") (pintype "output"))
      (node (ref "E4") (pin "10") (pinfunction "I1_10") (pintype "input"))
    )
    (net (code "8") (name "1L") (class "Default")
      (node (ref "E2") (pin "11") (pinfunction "CLK_11") (pintype "input"))
      (node (ref "E5") (pin "12") (pinfunction "D_12") (pintype "input"))
      (node (ref "E5") (pin "8") (pinfunction "~{Q}_8") (pintype "output"))
      (node (ref "E7") (pin "13") (pinfunction "I1_13") (pintype "input"))
    )
    (net (code "9") (name "2BIT") (class "Default")
      (node (ref "E1") (pin "12") (pinfunction "O_12") (pintype "output"))
      (node (ref "E4") (pin "12") (pinfunction "I2_12") (pintype "input"))
    )
    (net (code "10") (name "2H") (class "Default")
      (node (ref "E1") (pin "11") (pinfunction "I2_11") (pintype "input"))
      (node (ref "E2") (pin "9") (pinfunction "Q_9") (pintype "output"))
      (node (ref "E4") (pin "1") (pinfunction "I0_1") (pintype "input"))
    )
    (net (code "11") (name "2L") (class "Default")
      (node (ref "E1") (pin "2") (pinfunction "I1_2") (pintype "input"))
      (node (ref "E1") (pin "3") (pinfunction "I0_3") (pintype "input"))
      (node (ref "E2") (pin "12") (pinfunction "D_12") (pintype "input"))
      (node (ref "E2") (pin "3") (pinfunction "CLK_3") (pintype "input"))
      (node (ref "E2") (pin "8") (pinfunction "~{Q}_8") (pintype "output"))
    )
    (net (code "12") (name "3BIT") (class "Default")
      (node (ref "E4") (pin "13") (pinfunction "I3_13") (pintype "input"))
      (node (ref "E4") (pin "6") (pinfunction "O_6") (pintype "output"))
    )
    (net (code "13") (name "4H") (class "Default")
      (node (ref "E1") (pin "1") (pinfunction "I0_1") (pintype "input"))
      (node (ref "E2") (pin "5") (pinfunction "Q_5") (pintype "output"))
      (node (ref "E4") (pin "2") (pinfunction "I1_2") (pintype "input"))
    )
    (net (code "14") (name "4L") (class "Default")
      (node (ref "E1") (pin "10") (pinfunction "I1_10") (pintype "input"))
      (node (ref "E1") (pin "4") (pinfunction "I1_4") (pintype "input"))
      (node (ref "E2") (pin "2") (pinfunction "D_2") (pintype "input"))
      (node (ref "E2") (pin "6") (pinfunction "~{Q}_6") (pintype "output"))
    )
    (net (code "15") (name "202_DETECT_L") (class "Default")
      (node (ref "E23") (pin "11") (pinfunction "I2_11") (pintype "input"))
      (node (ref "E24") (pin "6") (pinfunction "O_6") (pintype "output"))
    )
    (net (code "16") (name "ADDRESS_INVALID_L") (class "Default")
      (node (ref "ADDR_INV") (pin "B") (pinfunction "B_B") (pintype "passive"))
      (node (ref "E21") (pin "5") (pinfunction "O_5") (pintype "open_collector"))
    )
    (net (code "17") (name "ADDR_COUNTER_1") (class "Default")
      (node (ref "E19") (pin "3") (pinfunction "QA_3") (pintype "output"))
      (node (ref "E26") (pin "5") (pinfunction "I1_5") (pintype "input"))
    )
    (net (code "18") (name "ADDR_COUNTER_2") (class "Default")
      (node (ref "E19") (pin "2") (pinfunction "QB_2") (pintype "output"))
      (node (ref "E24") (pin "1") (pinfunction "I0_1") (pintype "input"))
      (node (ref "E26") (pin "1") (pinfunction "I0_1") (pintype "input"))
    )
    (net (code "19") (name "ADDR_COUNTER_4") (class "Default")
      (node (ref "E19") (pin "6") (pinfunction "QC_6") (pintype "output"))
      (node (ref "E27") (pin "5") (pinfunction "I1_5") (pintype "input"))
    )
    (net (code "20") (name "ADDR_COUNTER_8") (class "Default")
      (node (ref "E19") (pin "7") (pinfunction "QD_7") (pintype "output"))
      (node (ref "E24") (pin "2") (pinfunction "I1_2") (pintype "input"))
      (node (ref "E27") (pin "1") (pinfunction "I0_1") (pintype "input"))
    )
    (net (code "21") (name "ADDR_COUNTER_16") (class "Default")
      (node (ref "E20") (pin "3") (pinfunction "QA_3") (pintype "output"))
      (node (ref "E28") (pin "5") (pinfunction "I1_5") (pintype "input"))
    )
    (net (code "22") (name "ADDR_COUNTER_32") (class "Default")
      (node (ref "E20") (pin "2") (pinfunction "QB_2") (pintype "output"))
      (node (ref "E23") (pin "3") (pinfunction "I0_3") (pintype "input"))
      (node (ref "E28") (pin "1") (pinfunction "I0_1") (pintype "input"))
    )
    (net (code "23") (name "ADDR_COUNTER_64") (class "Default")
      (node (ref "E20") (pin "6") (pinfunction "QC_6") (pintype "output"))
      (node (ref "E23") (pin "4") (pinfunction "I1_4") (pintype "input"))
      (node (ref "E24") (pin "4") (pinfunction "I2_4") (pintype "input"))
      (node (ref "E29") (pin "5") (pinfunction "I1_5") (pintype "input"))
    )
    (net (code "24") (name "ADDR_COUNTER_128") (class "Default")
      (node (ref "E20") (pin "7") (pinfunction "QD_7") (pintype "output"))
      (node (ref "E23") (pin "5") (pinfunction "I2_5") (pintype "input"))
      (node (ref "E24") (pin "5") (pinfunction "I3_5") (pintype "input"))
      (node (ref "E29") (pin "1") (pinfunction "I0_1") (pintype "input"))
    )
    (net (code "25") (name "ADDR_SOURCE_H") (class "Default")
      (node (ref "E18") (pin "5") (pinfunction "Q_5") (pintype "output"))
      (node (ref "E26") (pin "10") (pinfunction "I1_10") (pintype "input"))
      (node (ref "E26") (pin "13") (pinfunction "I1_13") (pintype "input"))
      (node (ref "E27") (pin "10") (pinfunction "I1_10") (pintype "input"))
      (node (ref "E27") (pin "13") (pinfunction "I1_13") (pintype "input"))
      (node (ref "E28") (pin "10") (pinfunction "I1_10") (pintype "input"))
      (node (ref "E28") (pin "13") (pinfunction "I1_13") (pintype "input"))
      (node (ref "E29") (pin "10") (pinfunction "I1_10") (pintype "input"))
      (node (ref "E29") (pin "13") (pinfunction "I1_13") (pintype "input"))
    )
    (net (code "26") (name "ADDR_SOURCE_L") (class "Default")
      (node (ref "E16") (pin "10") (pinfunction "I1_10") (pintype "input"))
      (node (ref "E16") (pin "4") (pinfunction "I1_4") (pintype "input"))
      (node (ref "E18") (pin "2") (pinfunction "D_2") (pintype "input"))
      (node (ref "E18") (pin "6") (pinfunction "~{Q}_6") (pintype "output"))
      (node (ref "E26") (pin "2") (pinfunction "I1_2") (pintype "input"))
      (node (ref "E26") (pin "4") (pinfunction "I0_4") (pintype "input"))
      (node (ref "E27") (pin "2") (pinfunction "I1_2") (pintype "input"))
      (node (ref "E27") (pin "4") (pinfunction "I0_4") (pintype "input"))
      (node (ref "E28") (pin "2") (pinfunction "I1_2") (pintype "input"))
      (node (ref "E28") (pin "4") (pinfunction "I0_4") (pintype "input"))
      (node (ref "E29") (pin "2") (pinfunction "I1_2") (pintype "input"))
      (node (ref "E29") (pin "4") (pinfunction "I0_4") (pintype "input"))
    )
    (net (code "27") (name "BIT_0L") (class "Default")
      (node (ref "BIT0") (pin "2") (pinfunction "P_2") (pintype "passive"))
      (node (ref "E1") (pin "5") (pinfunction "I2_5") (pintype "input"))
    )
    (net (code "28") (name "BIT_1L") (class "Default")
      (node (ref "BIT1") (pin "2") (pinfunction "P_2") (pintype "passive"))
      (node (ref "E1") (pin "9") (pinfunction "I0_9") (pintype "input"))
    )
    (net (code "29") (name "BIT_2L") (class "Default")
      (node (ref "BIT2") (pin "2") (pinfunction "P_2") (pintype "passive"))
      (node (ref "E1") (pin "13") (pinfunction "I2_13") (pintype "input"))
    )
    (net (code "30") (name "BIT_3L") (class "Default")
      (node (ref "BIT3") (pin "2") (pinfunction "P_2") (pintype "passive"))
      (node (ref "E4") (pin "5") (pinfunction "I3_5") (pintype "input"))
    )
    (net (code "31") (name "BUS_AC_LO_L") (class "Default")
      (node (ref "C39") (pin "1") (pinfunction "1_1") (pintype "passive"))
      (node (ref "J1") (pin "VV") (pinfunction "P$2_VV") (pintype "bidirectional"))
      (node (ref "R46") (pin "1") (pinfunction "1_1") (pintype "passive"))
    )
    (net (code "32") (name "BUS_ADDRESS_INVALID_L") (class "Default")
      (node (ref "E17") (pin "5") (pinfunction "I1_5") (pintype "input"))
      (node (ref "J2") (pin "C") (pinfunction "P$2_C") (pintype "bidirectional"))
      (node (ref "R26") (pin "1") (pinfunction "1_1") (pintype "passive"))
      (node (ref "RN3") (pin "3") (pinfunction "2_3") (pintype "passive"))
      (node (ref "RN7") (pin "3") (pinfunction "2_3") (pintype "passive"))
    )
    (net (code "33") (name "BUS_ADDR_ACCEPTED_L") (class "Default")
      (node (ref "J2") (pin "H") (pinfunction "P$2_H") (pintype "bidirectional"))
      (node (ref "RN3") (pin "5") (pinfunction "2_5") (pintype "passive"))
      (node (ref "RN7") (pin "5") (pinfunction "2_5") (pintype "passive"))
    )
    (net (code "34") (name "BUS_CA_00_L") (class "Default")
      (node (ref "E30") (pin "5") (pinfunction "O_5") (pintype "open_collector"))
      (node (ref "J2") (pin "Y") (pinfunction "P$2_Y") (pintype "bidirectional"))
      (node (ref "R147") (pin "1") (pinfunction "1_1") (pintype "passive"))
      (node (ref "R148") (pin "2") (pinfunction "2_2") (pintype "passive"))
    )
    (net (code "35") (name "BUS_CA_01_L") (class "Default")
      (node (ref "E30") (pin "3") (pinfunction "O_3") (pintype "open_collector"))
      (node (ref "J2") (pin "SS") (pinfunction "P$2_SS") (pintype "bidirectional"))
      (node (ref "RN4") (pin "3") (pinfunction "2_3") (pintype "passive"))
      (node (ref "RN8") (pin "3") (pinfunction "2_3") (pintype "passive"))
    )
    (net (code "36") (name "BUS_CA_02_L") (class "Default")
      (node (ref "E31") (pin "5") (pinfunction "O_5") (pintype "open_collector"))
      (node (ref "J2") (pin "U") (pinfunction "P$2_U") (pintype "bidirectional"))
      (node (ref "RN3") (pin "10") (pinfunction "2_10") (pintype "passive"))
      (node (ref "RN7") (pin "10") (pinfunction "2_10") (pintype "passive"))
    )
    (net (code "37") (name "BUS_CA_03_L") (class "Default")
      (node (ref "E31") (pin "3") (pinfunction "O_3") (pintype "open_collector"))
      (node (ref "J2") (pin "UU") (pinfunction "P$2_UU") (pintype "bidirectional"))
      (node (ref "RN4") (pin "2") (pinfunction "2_2") (pintype "passive"))
      (node (ref "RN8") (pin "2") (pinfunction "2_2") (pintype "passive"))
    )
    (net (code "38") (name "BUS_CA_04_L") (class "Default")
      (node (ref "E32") (pin "5") (pinfunction "O_5") (pintype "open_collector"))
      (node (ref "J2") (pin "MM") (pinfunction "P$2_MM") (pintype "bidirectional"))
      (node (ref "RN4") (pin "5") (pinfunction "2_5") (pintype "passive"))
      (node (ref "RN8") (pin "5") (pinfunction "2_5") (pintype "passive"))
    )
    (net (code "39") (name "BUS_CA_05_L") (class "Default")
      (node (ref "E32") (pin "3") (pinfunction "O_3") (pintype "open_collector"))
      (node (ref "J2") (pin "CC") (pinfunction "P$2_CC") (pintype "bidirectional"))
      (node (ref "RN4") (pin "9") (pinfunction "2_9") (pintype "passive"))
      (node (ref "RN8") (pin "9") (pinfunction "2_9") (pintype "passive"))
    )
    (net (code "40") (name "BUS_CA_06_L") (class "Default")
      (node (ref "E33") (pin "5") (pinfunction "O_5") (pintype "open_collector"))
      (node (ref "J2") (pin "PP") (pinfunction "P$2_PP") (pintype "bidirectional"))
      (node (ref "RN4") (pin "4") (pinfunction "2_4") (pintype "passive"))
      (node (ref "RN8") (pin "4") (pinfunction "2_4") (pintype "passive"))
    )
    (net (code "41") (name "BUS_CA_07_L") (class "Default")
      (node (ref "E33") (pin "3") (pinfunction "O_3") (pintype "open_collector"))
      (node (ref "J2") (pin "HH") (pinfunction "P$2_HH") (pintype "bidirectional"))
      (node (ref "RN4") (pin "7") (pinfunction "2_7") (pintype "passive"))
      (node (ref "RN8") (pin "7") (pinfunction "2_7") (pintype "passive"))
    )
    (net (code "42") (name "BUS_DATA&CLOCK_L") (class "Default")
      (node (ref "E9") (pin "10") (pinfunction "O_10") (pintype "open_collector"))
      (node (ref "J2") (pin "KK") (pinfunction "P$2_KK") (pintype "bidirectional"))
      (node (ref "RN4") (pin "6") (pinfunction "2_6") (pintype "passive"))
      (node (ref "RN8") (pin "6") (pinfunction "2_6") (pintype "passive"))
    )
    (net (code "43") (name "BUS_DC_LO_L") (class "Default")
      (node (ref "C53") (pin "1") (pinfunction "1_1") (pintype "passive"))
      (node (ref "J1") (pin "TT") (pinfunction "P$2_TT") (pintype "bidirectional"))
      (node (ref "R50") (pin "1") (pinfunction "1_1") (pintype "passive"))
    )
    (net (code "44") (name "BUS_FILE_READY") (class "Default")
      (node (ref "J1") (pin "V") (pinfunction "P$2_V") (pintype "bidirectional"))
      (node (ref "RN1") (pin "9") (pinfunction "2_9") (pintype "passive"))
      (node (ref "RN5") (pin "9") (pinfunction "2_9") (pintype "passive"))
    )
    (net (code "45") (name "BUS_HIGH_DENSITY_L") (class "Default")
      (node (ref "J1") (pin "N") (pinfunction "P$2_N") (pintype "bidirectional"))
      (node (ref "RN1") (pin "6") (pinfunction "2_6") (pintype "passive"))
      (node (ref "RN5") (pin "6") (pinfunction "2_6") (pintype "passive"))
    )
    (net (code "46") (name "BUS_INDEX_L") (class "Default")
      (node (ref "E11") (pin "1") (pinfunction "CLR_1") (pintype "input"))
      (node (ref "E11") (pin "11") (pinfunction "CLK_11") (pintype "input"))
      (node (ref "J1") (pin "Z") (pinfunction "P$2_Z") (pintype "bidirectional"))
      (node (ref "RN2") (pin "10") (pinfunction "2_10") (pintype "passive"))
      (node (ref "RN6") (pin "10") (pinfunction "2_10") (pintype "passive"))
    )
    (net (code "47") (name "BUS_READ_GATE_L") (class "Default")
      (node (ref "J1") (pin "L") (pinfunction "P$2_L") (pintype "bidirectional"))
      (node (ref "RN1") (pin "5") (pinfunction "2_5") (pintype "passive"))
      (node (ref "RN5") (pin "5") (pinfunction "2_5") (pintype "passive"))
    )
    (net (code "48") (name "BUS_RESTORE_L") (class "Default")
      (node (ref "C34") (pin "1") (pinfunction "1_1") (pintype "passive"))
      (node (ref "E22") (pin "5") (pinfunction "O_5") (pintype "open_collector"))
      (node (ref "J2") (pin "P") (pinfunction "P$2_P") (pintype "bidirectional"))
      (node (ref "RN3") (pin "8") (pinfunction "2_8") (pintype "passive"))
      (node (ref "RN7") (pin "8") (pinfunction "2_8") (pintype "passive"))
    )
    (net (code "49") (name "BUS_RWS_READY_L") (class "Default")
      (node (ref "E12") (pin "5") (pinfunction "I_5") (pintype "input"))
      (node (ref "J2") (pin "EE") (pinfunction "P$2_EE") (pintype "bidirectional"))
      (node (ref "RN4") (pin "8") (pinfunction "2_8") (pintype "passive"))
      (node (ref "RN8") (pin "8") (pinfunction "2_8") (pintype "passive"))
    )
    (net (code "50") (name "BUS_SECTOR_ADDR_0L") (class "Default")
      (node (ref "E6") (pin "5") (pinfunction "I_5") (pintype "input"))
      (node (ref "J1") (pin "DD") (pinfunction "P$2_DD") (pintype "bidirectional"))
      (node (ref "R17") (pin "1") (pinfunction "1_1") (pintype "passive"))
      (node (ref "RN2") (pin "8") (pinfunction "2_8") (pintype "passive"))
      (node (ref "RN6") (pin "8") (pinfunction "2_8") (pintype "passive"))
    )
    (net (code "51") (name "BUS_SECTOR_ADDR_1L") (class "Default")
      (node (ref "E6") (pin "13") (pinfunction "I_13") (pintype "input"))
      (node (ref "J2") (pin "K") (pinfunction "P$2_K") (pintype "bidirectional"))
      (node (ref "R18") (pin "1") (pinfunction "1_1") (pintype "passive"))
      (node (ref "RN3") (pin "6") (pinfunction "2_6") (pintype "passive"))
      (node (ref "RN7") (pin "6") (pinfunction "2_6") (pintype "passive"))
    )
    (net (code "52") (name "BUS_SECTOR_ADDR_2L") (class "Default")
      (node (ref "E6") (pin "11") (pinfunction "I_11") (pintype "input"))
      (node (ref "J1") (pin "FF") (pinfunction "P$2_FF") (pintype "bidirectional"))
      (node (ref "R16") (pin "1") (pinfunction "1_1") (pintype "passive"))
      (node (ref "RN2") (pin "7") (pinfunction "2_7") (pintype "passive"))
      (node (ref "RN6") (pin "7") (pinfunction "2_7") (pintype "passive"))
    )
    (net (code "53") (name "BUS_SECTOR_ADDR_3L") (class "Default")
      (node (ref "E6") (pin "9") (pinfunction "I_9") (pintype "input"))
      (node (ref "J1") (pin "LL") (pinfunction "P$2_LL") (pintype "bidirectional"))
      (node (ref "R11") (pin "1") (pinfunction "1_1") (pintype "passive"))
      (node (ref "RN2") (pin "5") (pinfunction "2_5") (pintype "passive"))
      (node (ref "RN6") (pin "5") (pinfunction "2_5") (pintype "passive"))
    )
    (net (code "54") (name "BUS_SECTOR_PULSE_L") (class "Default")
      (node (ref "J1") (pin "T") (pinfunction "P$2_T") (pintype "bidirectional"))
      (node (ref "RN1") (pin "8") (pinfunction "2_8") (pintype "passive"))
      (node (ref "RN5") (pin "8") (pinfunction "2_8") (pintype "passive"))
    )
    (net (code "55") (name "BUS_SEEK_INCOMPLETE_L") (class "Default")
      (node (ref "E21") (pin "7") (pinfunction "I1_7") (pintype "input"))
      (node (ref "J2") (pin "E") (pinfunction "P$2_E") (pintype "bidirectional"))
      (node (ref "R27") (pin "1") (pinfunction "1_1") (pintype "passive"))
      (node (ref "RN3") (pin "4") (pinfunction "2_4") (pintype "passive"))
      (node (ref "RN7") (pin "4") (pinfunction "2_4") (pintype "passive"))
    )
    (net (code "56") (name "BUS_STROBE_L") (class "Default")
      (node (ref "E22") (pin "3") (pinfunction "O_3") (pintype "open_collector"))
      (node (ref "J1") (pin "RR") (pinfunction "P$2_RR") (pintype "bidirectional"))
      (node (ref "RN2") (pin "3") (pinfunction "2_3") (pintype "passive"))
      (node (ref "RN6") (pin "3") (pinfunction "2_3") (pintype "passive"))
    )
    (net (code "57") (name "BUS_WP_SET_L") (class "Default")
      (node (ref "J1") (pin "J") (pinfunction "P$2_J") (pintype "bidirectional"))
      (node (ref "RN1") (pin "4") (pinfunction "2_4") (pintype "passive"))
      (node (ref "RN5") (pin "4") (pinfunction "2_4") (pintype "passive"))
    )
    (net (code "58") (name "BUS_WP_STATUS_L") (class "Default")
      (node (ref "J1") (pin "R") (pinfunction "P$2_R") (pintype "bidirectional"))
      (node (ref "RN1") (pin "7") (pinfunction "2_7") (pintype "passive"))
      (node (ref "RN5") (pin "7") (pinfunction "2_7") (pintype "passive"))
    )
    (net (code "59") (name "BUS_WRITE_CK") (class "Default")
      (node (ref "J1") (pin "JJ") (pinfunction "P$2_JJ") (pintype "bidirectional"))
      (node (ref "RN2") (pin "6") (pinfunction "2_6") (pintype "passive"))
      (node (ref "RN6") (pin "6") (pinfunction "2_6") (pintype "passive"))
    )
    (net (code "60") (name "BUS_WRITE_GATE_L") (class "Default")
      (node (ref "E9") (pin "13") (pinfunction "O_13") (pintype "open_collector"))
      (node (ref "J1") (pin "BB") (pinfunction "P$2_BB") (pintype "bidirectional"))
      (node (ref "RN2") (pin "9") (pinfunction "2_9") (pintype "passive"))
      (node (ref "RN6") (pin "9") (pinfunction "2_9") (pintype "passive"))
    )
    (net (code "61") (name "CA_SW_1") (class "Default")
      (node (ref "CYL1") (pin "3") (pinfunction "S_3") (pintype "passive"))
      (node (ref "E26") (pin "9") (pinfunction "I0_9") (pintype "input"))
      (node (ref "R45") (pin "2") (pinfunction "2_2") (pintype "passive"))
    )
    (net (code "62") (name "CA_SW_2") (class "Default")
      (node (ref "CYL2") (pin "3") (pinfunction "S_3") (pintype "passive"))
      (node (ref "E26") (pin "12") (pinfunction "I0_12") (pintype "input"))
      (node (ref "R44") (pin "2") (pinfunction "2_2") (pintype "passive"))
    )
    (net (code "63") (name "CA_SW_4") (class "Default")
      (node (ref "CYL4") (pin "3") (pinfunction "S_3") (pintype "passive"))
      (node (ref "E27") (pin "9") (pinfunction "I0_9") (pintype "input"))
      (node (ref "R43") (pin "2") (pinfunction "2_2") (pintype "passive"))
    )
    (net (code "64") (name "CA_SW_8") (class "Default")
      (node (ref "CYL8") (pin "3") (pinfunction "S_3") (pintype "passive"))
      (node (ref "E27") (pin "12") (pinfunction "I0_12") (pintype "input"))
      (node (ref "R42") (pin "2") (pinfunction "2_2") (pintype "passive"))
    )
    (net (code "65") (name "CA_SW_16") (class "Default")
      (node (ref "CYL16") (pin "3") (pinfunction "S_3") (pintype "passive"))
      (node (ref "E28") (pin "9") (pinfunction "I0_9") (pintype "input"))
      (node (ref "R41") (pin "2") (pinfunction "2_2") (pintype "passive"))
    )
    (net (code "66") (name "CA_SW_32") (class "Default")
      (node (ref "CYL32") (pin "3") (pinfunction "S_3") (pintype "passive"))
      (node (ref "E28") (pin "12") (pinfunction "I0_12") (pintype "input"))
      (node (ref "R40") (pin "2") (pinfunction "2_2") (pintype "passive"))
    )
    (net (code "67") (name "CA_SW_64") (class "Default")
      (node (ref "CYL64") (pin "3") (pinfunction "S_3") (pintype "passive"))
      (node (ref "E29") (pin "9") (pinfunction "I0_9") (pintype "input"))
      (node (ref "R39") (pin "2") (pinfunction "2_2") (pintype "passive"))
    )
    (net (code "68") (name "CA_SW_128") (class "Default")
      (node (ref "CYL128") (pin "3") (pinfunction "S_3") (pintype "passive"))
      (node (ref "E29") (pin "12") (pinfunction "I0_12") (pintype "input"))
      (node (ref "R38") (pin "2") (pinfunction "2_2") (pintype "passive"))
    )
    (net (code "69") (name "CLOCK_H") (class "Default")
      (node (ref "E7") (pin "10") (pinfunction "I1_10") (pintype "input"))
      (node (ref "E7") (pin "12") (pinfunction "I0_12") (pintype "input"))
      (node (ref "E8") (pin "1") (pinfunction "A_1") (pintype "input"))
      (node (ref "E8") (pin "5") (pinfunction "Q_5") (pintype "output"))
    )
    (net (code "70") (name "CONSTANT_WRITE_L") (class "Default")
      (node (ref "CONSTANT_WRITE") (pin "2") (pinfunction "P_2") (pintype "passive"))
      (node (ref "E11") (pin "4") (pinfunction "PRE_4") (pintype "input"))
    )
    (net (code "71") (name "DC_ERASE") (class "Default")
      (node (ref "DC_ERASE") (pin "2") (pinfunction "P_2") (pintype "passive"))
      (node (ref "E9") (pin "8") (pinfunction "I0_8") (pintype "input"))
    )
    (net (code "72") (name "FWD_L") (class "Default")
      (node (ref "E16") (pin "9") (pinfunction "I0_9") (pintype "input"))
      (node (ref "E17") (pin "9") (pinfunction "I0_9") (pintype "input"))
      (node (ref "FWD/REV") (pin "3") (pinfunction "S_3") (pintype "passive"))
      (node (ref "R36") (pin "1") (pinfunction "1_1") (pintype "passive"))
    )
    (net (code "73") (name "GND") (class "Default")
      (node (ref "BIT0") (pin "1") (pinfunction "O_1") (pintype "passive"))
      (node (ref "BIT1") (pin "1") (pinfunction "O_1") (pintype "passive"))
      (node (ref "BIT2") (pin "1") (pinfunction "O_1") (pintype "passive"))
      (node (ref "BIT3") (pin "1") (pinfunction "O_1") (pintype "passive"))
      (node (ref "C1") (pin "2") (pinfunction "2_2") (pintype "passive"))
      (node (ref "C10") (pin "2") (pinfunction "2_2") (pintype "passive"))
      (node (ref "C11") (pin "2") (pinfunction "2_2") (pintype "passive"))
      (node (ref "C12") (pin "2") (pinfunction "2_2") (pintype "passive"))
      (node (ref "C13") (pin "2") (pinfunction "2_2") (pintype "passive"))
      (node (ref "C14") (pin "2") (pinfunction "2_2") (pintype "passive"))
      (node (ref "C15") (pin "2") (pinfunction "2_2") (pintype "passive"))
      (node (ref "C16") (pin "2") (pinfunction "2_2") (pintype "passive"))
      (node (ref "C17") (pin "2") (pinfunction "2_2") (pintype "passive"))
      (node (ref "C18") (pin "2") (pinfunction "2_2") (pintype "passive"))
      (node (ref "C19") (pin "2") (pinfunction "2_2") (pintype "passive"))
      (node (ref "C2") (pin "2") (pinfunction "2_2") (pintype "passive"))
      (node (ref "C20") (pin "2") (pinfunction "2_2") (pintype "passive"))
      (node (ref "C21") (pin "2") (pinfunction "2_2") (pintype "passive"))
      (node (ref "C22") (pin "2") (pinfunction "2_2") (pintype "passive"))
      (node (ref "C23") (pin "2") (pinfunction "2_2") (pintype "passive"))
      (node (ref "C24") (pin "2") (pinfunction "2_2") (pintype "passive"))
      (node (ref "C26") (pin "2") (pinfunction "2_2") (pintype "passive"))
      (node (ref "C27") (pin "2") (pinfunction "2_2") (pintype "passive"))
      (node (ref "C28") (pin "2") (pinfunction "2_2") (pintype "passive"))
      (node (ref "C29") (pin "2") (pinfunction "2_2") (pintype "passive"))
      (node (ref "C3") (pin "2") (pinfunction "2_2") (pintype "passive"))
      (node (ref "C30") (pin "2") (pinfunction "2_2") (pintype "passive"))
      (node (ref "C31") (pin "2") (pinfunction "2_2") (pintype "passive"))
      (node (ref "C32") (pin "2") (pinfunction "2_2") (pintype "passive"))
      (node (ref "C33") (pin "2") (pinfunction "2_2") (pintype "passive"))
      (node (ref "C34") (pin "2") (pinfunction "2_2") (pintype "passive"))
      (node (ref "C36") (pin "2") (pinfunction "2_2") (pintype "passive"))
      (node (ref "C38") (pin "2") (pinfunction "2_2") (pintype "passive"))
      (node (ref "C39") (pin "2") (pinfunction "2_2") (pintype "passive"))
      (node (ref "C4") (pin "2") (pinfunction "2_2") (pintype "passive"))
      (node (ref "C40") (pin "2") (pinfunction "2_2") (pintype "passive"))
      (node (ref "C41") (pin "2") (pinfunction "2_2") (pintype "passive"))
      (node (ref "C42") (pin "2") (pinfunction "2_2") (pintype "passive"))
      (node (ref "C43") (pin "2") (pinfunction "2_2") (pintype "passive"))
      (node (ref "C44") (pin "-") (pinfunction "-_-") (pintype "passive"))
      (node (ref "C45") (pin "+") (pinfunction "+_+") (pintype "passive"))
      (node (ref "C5") (pin "2") (pinfunction "2_2") (pintype "passive"))
      (node (ref "C52") (pin "-") (pinfunction "-_-") (pintype "passive"))
      (node (ref "C53") (pin "2") (pinfunction "2_2") (pintype "passive"))
      (node (ref "C6") (pin "2") (pinfunction "2_2") (pintype "passive"))
      (node (ref "C60") (pin "-") (pinfunction "-_-") (pintype "passive"))
      (node (ref "C61") (pin "-") (pinfunction "-_-") (pintype "passive"))
      (node (ref "C67") (pin "-") (pinfunction "-_-") (pintype "passive"))
      (node (ref "C68") (pin "-") (pinfunction "-_-") (pintype "passive"))
      (node (ref "C7") (pin "2") (pinfunction "2_2") (pintype "passive"))
      (node (ref "C8") (pin "2") (pinfunction "2_2") (pintype "passive"))
      (node (ref "C9") (pin "2") (pinfunction "2_2") (pintype "passive"))
      (node (ref "CONSTANT_WRITE") (pin "3") (pinfunction "S_3") (pintype "passive"))
      (node (ref "CYL1") (pin "2") (pinfunction "P_2") (pintype "passive"))
      (node (ref "CYL128") (pin "2") (pinfunction "P_2") (pintype "passive"))
      (node (ref "CYL16") (pin "2") (pinfunction "P_2") (pintype "passive"))
      (node (ref "CYL2") (pin "2") (pinfunction "P_2") (pintype "passive"))
      (node (ref "CYL32") (pin "2") (pinfunction "P_2") (pintype "passive"))
      (node (ref "CYL4") (pin "2") (pinfunction "P_2") (pintype "passive"))
      (node (ref "CYL64") (pin "2") (pinfunction "P_2") (pintype "passive"))
      (node (ref "CYL8") (pin "2") (pinfunction "P_2") (pintype "passive"))
      (node (ref "D5") (pin "A") (pinfunction "A_A") (pintype "passive"))
      (node (ref "DC_ERASE") (pin "3") (pinfunction "S_3") (pintype "passive"))
      (node (ref "DRIVE") (pin "C1") (pinfunction "A_C1") (pintype "passive"))
      (node (ref "E12") (pin "9") (pinfunction "I_9") (pintype "input"))
      (node (ref "E14") (pin "1") (pinfunction "A_1") (pintype "input"))
      (node (ref "E14") (pin "9") (pinfunction "A_9") (pintype "input"))
      (node (ref "E15") (pin "10") (pinfunction "I1_10") (pintype "input"))
      (node (ref "E15") (pin "12") (pinfunction "I0_12") (pintype "input"))
      (node (ref "E15") (pin "13") (pinfunction "I1_13") (pintype "input"))
      (node (ref "E15") (pin "4") (pinfunction "I0_4") (pintype "input"))
      (node (ref "E15") (pin "5") (pinfunction "I1_5") (pintype "input"))
      (node (ref "E15") (pin "9") (pinfunction "I0_9") (pintype "input"))
      (node (ref "E19") (pin "10") (pinfunction "C_10") (pintype "input"))
      (node (ref "E19") (pin "15") (pinfunction "A_15") (pintype "input"))
      (node (ref "E20") (pin "1") (pinfunction "B_1") (pintype "input"))
      (node (ref "E20") (pin "15") (pinfunction "A_15") (pintype "input"))
      (node (ref "E24") (pin "10") (pinfunction "I1_10") (pintype "input"))
      (node (ref "E24") (pin "12") (pinfunction "I2_12") (pintype "input"))
      (node (ref "E24") (pin "13") (pinfunction "I3_13") (pintype "input"))
      (node (ref "E24") (pin "9") (pinfunction "I0_9") (pintype "input"))
      (node (ref "E5") (pin "2") (pinfunction "D_2") (pintype "input"))
      (node (ref "E5") (pin "3") (pinfunction "CLK_3") (pintype "input"))
      (node (ref "E6") (pin "1") (pinfunction "I_1") (pintype "input"))
      (node (ref "E8") (pin "9") (pinfunction "A_9") (pintype "input"))
      (node (ref "E9") (pin "2") (pinfunction "I0_2") (pintype "input"))
      (node (ref "E9") (pin "3") (pinfunction "I1_3") (pintype "input"))
      (node (ref "E9") (pin "5") (pinfunction "I0_5") (pintype "input"))
      (node (ref "E9") (pin "6") (pinfunction "I1_6") (pintype "input"))
      (node (ref "FUNCTION") (pin "C1") (pinfunction "A_C1") (pintype "passive"))
      (node (ref "FWD/REV") (pin "2") (pinfunction "P_2") (pintype "passive"))
      (node (ref "HEAD") (pin "3") (pinfunction "S_3") (pintype "passive"))
      (node (ref "J1") (pin "A") (pinfunction "P$2_A") (pintype "bidirectional"))
      (node (ref "J1") (pin "AA") (pinfunction "P$2_AA") (pintype "bidirectional"))
      (node (ref "J1") (pin "B") (pinfunction "P$2_B") (pintype "bidirectional"))
      (node (ref "J1") (pin "C") (pinfunction "P$2_C") (pintype "bidirectional"))
      (node (ref "J1") (pin "CC") (pinfunction "P$2_CC") (pintype "bidirectional"))
      (node (ref "J1") (pin "E") (pinfunction "P$2_E") (pintype "bidirectional"))
      (node (ref "J1") (pin "EE") (pinfunction "P$2_EE") (pintype "bidirectional"))
      (node (ref "J1") (pin "H") (pinfunction "P$2_H") (pintype "bidirectional"))
      (node (ref "J1") (pin "HH") (pinfunction "P$2_HH") (pintype "bidirectional"))
      (node (ref "J1") (pin "K") (pinfunction "P$2_K") (pintype "bidirectional"))
      (node (ref "J1") (pin "KK") (pinfunction "P$2_KK") (pintype "bidirectional"))
      (node (ref "J1") (pin "M") (pinfunction "P$2_M") (pintype "bidirectional"))
      (node (ref "J1") (pin "MM") (pinfunction "P$2_MM") (pintype "bidirectional"))
      (node (ref "J1") (pin "P") (pinfunction "P$2_P") (pintype "bidirectional"))
      (node (ref "J1") (pin "PP") (pinfunction "P$2_PP") (pintype "bidirectional"))
      (node (ref "J1") (pin "S") (pinfunction "P$2_S") (pintype "bidirectional"))
      (node (ref "J1") (pin "SS") (pinfunction "P$2_SS") (pintype "bidirectional"))
      (node (ref "J1") (pin "U") (pinfunction "P$2_U") (pintype "bidirectional"))
      (node (ref "J1") (pin "UU") (pinfunction "P$2_UU") (pintype "bidirectional"))
      (node (ref "J1") (pin "W") (pinfunction "P$2_W") (pintype "bidirectional"))
      (node (ref "J1") (pin "Y") (pinfunction "P$2_Y") (pintype "bidirectional"))
      (node (ref "J2") (pin "B") (pinfunction "P$2_B") (pintype "bidirectional"))
      (node (ref "J2") (pin "BB") (pinfunction "P$2_BB") (pintype "bidirectional"))
      (node (ref "J2") (pin "D") (pinfunction "P$2_D") (pintype "bidirectional"))
      (node (ref "J2") (pin "DD") (pinfunction "P$2_DD") (pintype "bidirectional"))
      (node (ref "J2") (pin "F") (pinfunction "P$2_F") (pintype "bidirectional"))
      (node (ref "J2") (pin "FF") (pinfunction "P$2_FF") (pintype "bidirectional"))
      (node (ref "J2") (pin "J") (pinfunction "P$2_J") (pintype "bidirectional"))
      (node (ref "J2") (pin "JJ") (pinfunction "P$2_JJ") (pintype "bidirectional"))
      (node (ref "J2") (pin "L") (pinfunction "P$2_L") (pintype "bidirectional"))
      (node (ref "J2") (pin "LL") (pinfunction "P$2_LL") (pintype "bidirectional"))
      (node (ref "J2") (pin "N") (pinfunction "P$2_N") (pintype "bidirectional"))
      (node (ref "J2") (pin "NN") (pinfunction "P$2_NN") (pintype "bidirectional"))
      (node (ref "J2") (pin "R") (pinfunction "P$2_R") (pintype "bidirectional"))
      (node (ref "J2") (pin "RR") (pinfunction "P$2_RR") (pintype "bidirectional"))
      (node (ref "J2") (pin "T") (pinfunction "P$2_T") (pintype "bidirectional"))
      (node (ref "J2") (pin "TT") (pinfunction "P$2_TT") (pintype "bidirectional"))
      (node (ref "J2") (pin "V") (pinfunction "P$2_V") (pintype "bidirectional"))
      (node (ref "J2") (pin "VV") (pinfunction "P$2_VV") (pintype "bidirectional"))
      (node (ref "J2") (pin "X") (pinfunction "P$2_X") (pintype "bidirectional"))
      (node (ref "J2") (pin "Z") (pinfunction "P$2_Z") (pintype "bidirectional"))
      (node (ref "POWER") (pin "1") (pinfunction "1_1") (pintype "passive"))
      (node (ref "POWER_ON") (pin "B") (pinfunction "B_B") (pintype "passive"))
      (node (ref "R14") (pin "1") (pinfunction "1_1") (pintype "passive"))
      (node (ref "R148") (pin "1") (pinfunction "1_1") (pintype "passive"))
      (node (ref "R15") (pin "1") (pinfunction "1_1") (pintype "passive"))
      (node (ref "R23") (pin "1") (pinfunction "1_1") (pintype "passive"))
      (node (ref "R31") (pin "1") (pinfunction "1_1") (pintype "passive"))
      (node (ref "R70") (pin "1") (pinfunction "1_1") (pintype "passive"))
      (node (ref "RN5") (pin "1") (pinfunction "1_1") (pintype "passive"))
      (node (ref "RN6") (pin "1") (pinfunction "1_1") (pintype "passive"))
      (node (ref "RN6") (pin "2") (pinfunction "2_2") (pintype "passive"))
      (node (ref "RN7") (pin "1") (pinfunction "1_1") (pintype "passive"))
      (node (ref "RN8") (pin "1") (pinfunction "1_1") (pintype "passive"))
      (node (ref "RTZ") (pin "2") (pinfunction "P_2") (pintype "passive"))
      (node (ref "SECTOR") (pin "11") (pinfunction "11_11") (pintype "passive"))
      (node (ref "SECTOR") (pin "12") (pinfunction "12_12") (pintype "passive"))
      (node (ref "WRITE_BUTTON") (pin "2") (pinfunction "P_2") (pintype "passive"))
    )
    (net (code "74") (name "HEAD_SELECT_L") (class "Default")
      (node (ref "HEAD") (pin "2") (pinfunction "P_2") (pintype "passive"))
      (node (ref "J1") (pin "X") (pinfunction "P$2_X") (pintype "bidirectional"))
      (node (ref "RN1") (pin "10") (pinfunction "2_10") (pintype "passive"))
      (node (ref "RN5") (pin "10") (pinfunction "2_10") (pintype "passive"))
    )
    (net (code "75") (name "NEG1_DETECT_L") (class "Default")
      (node (ref "E23") (pin "10") (pinfunction "I1_10") (pintype "input"))
      (node (ref "E23") (pin "6") (pinfunction "O_6") (pintype "output"))
    )
    (net (code "76") (name "Net-(ADDR_INV-PadA)") (class "Default")
      (node (ref "ADDR_INV") (pin "A") (pinfunction "A_A") (pintype "passive"))
      (node (ref "R1") (pin "1") (pinfunction "1_1") (pintype "passive"))
    )
    (net (code "77") (name "Net-(BIT0-S)") (class "Default")
      (node (ref "BIT0") (pin "3") (pinfunction "S_3") (pintype "passive"))
      (node (ref "BIT1") (pin "3") (pinfunction "S_3") (pintype "passive"))
      (node (ref "BIT2") (pin "3") (pinfunction "S_3") (pintype "passive"))
      (node (ref "BIT3") (pin "3") (pinfunction "S_3") (pintype "passive"))
      (node (ref "R7") (pin "1") (pinfunction "1_1") (pintype "passive"))
    )
    (net (code "78") (name "Net-(CONSTANT_WRITE-O)") (class "Default")
      (node (ref "CONSTANT_WRITE") (pin "1") (pinfunction "O_1") (pintype "passive"))
      (node (ref "E11") (pin "10") (pinfunction "PRE_10") (pintype "input"))
      (node (ref "E11") (pin "2") (pinfunction "D_2") (pintype "input"))
      (node (ref "R4") (pin "1") (pinfunction "1_1") (pintype "passive"))
    )
    (net (code "79") (name "Net-(D2-PadC)") (class "Default")
      (node (ref "D2") (pin "C") (pinfunction "C_C") (pintype "passive"))
      (node (ref "D3") (pin "A") (pinfunction "A_A") (pintype "passive"))
    )
    (net (code "80") (name "Net-(D3-PadC)") (class "Default")
      (node (ref "D3") (pin "C") (pinfunction "C_C") (pintype "passive"))
      (node (ref "D4") (pin "A") (pinfunction "A_A") (pintype "passive"))
    )
    (net (code "81") (name "Net-(E2A-PRE)") (class "Default")
      (node (ref "E2") (pin "10") (pinfunction "PRE_10") (pintype "input"))
      (node (ref "E2") (pin "4") (pinfunction "PRE_4") (pintype "input"))
      (node (ref "E5") (pin "10") (pinfunction "PRE_10") (pintype "input"))
      (node (ref "R10") (pin "1") (pinfunction "1_1") (pintype "passive"))
    )
    (net (code "82") (name "Net-(E3A-A)") (class "Default")
      (node (ref "E3") (pin "15") (pinfunction "A_15") (pintype "input"))
      (node (ref "E6") (pin "6") (pinfunction "O_6") (pintype "output"))
    )
    (net (code "83") (name "Net-(E3A-B)") (class "Default")
      (node (ref "E3") (pin "14") (pinfunction "B_14") (pintype "input"))
      (node (ref "E6") (pin "12") (pinfunction "O_12") (pintype "output"))
    )
    (net (code "84") (name "Net-(E3A-C)") (class "Default")
      (node (ref "E3") (pin "13") (pinfunction "C_13") (pintype "input"))
      (node (ref "E6") (pin "10") (pinfunction "O_10") (pintype "output"))
    )
    (net (code "85") (name "Net-(E3A-D)") (class "Default")
      (node (ref "E3") (pin "12") (pinfunction "D_12") (pintype "input"))
      (node (ref "E6") (pin "8") (pinfunction "O_8") (pintype "output"))
    )
    (net (code "86") (name "Net-(E4B-O)") (class "Default")
      (node (ref "E4") (pin "8") (pinfunction "O_8") (pintype "output"))
      (node (ref "E7") (pin "9") (pinfunction "I0_9") (pintype "input"))
    )
    (net (code "87") (name "Net-(E5B-CLK)") (class "Default")
      (node (ref "E5") (pin "11") (pinfunction "CLK_11") (pintype "input"))
      (node (ref "E8") (pin "12") (pinfunction "~{Q}_12") (pintype "output"))
    )
    (net (code "88") (name "Net-(E6A-O)") (class "Default")
      (node (ref "E6") (pin "2") (pinfunction "O_2") (pintype "output"))
      (node (ref "E6") (pin "3") (pinfunction "I_3") (pintype "input"))
    )
    (net (code "89") (name "Net-(E7A-O)") (class "Default")
      (node (ref "E7") (pin "3") (pinfunction "O_3") (pintype "output"))
      (node (ref "E9") (pin "12") (pinfunction "I1_12") (pintype "input"))
    )
    (net (code "90") (name "Net-(E7B-I0)") (class "Default")
      (node (ref "E7") (pin "11") (pinfunction "O_11") (pintype "output"))
      (node (ref "E7") (pin "4") (pinfunction "I0_4") (pintype "input"))
    )
    (net (code "91") (name "Net-(E7B-I1)") (class "Default")
      (node (ref "E7") (pin "5") (pinfunction "I1_5") (pintype "input"))
      (node (ref "E7") (pin "8") (pinfunction "O_8") (pintype "output"))
    )
    (net (code "92") (name "Net-(E7B-O)") (class "Default")
      (node (ref "E7") (pin "6") (pinfunction "O_6") (pintype "output"))
      (node (ref "E9") (pin "9") (pinfunction "I1_9") (pintype "input"))
    )
    (net (code "93") (name "Net-(E8A-C)") (class "Default")
      (node (ref "C63") (pin "2") (pinfunction "2_2") (pintype "passive"))
      (node (ref "E8") (pin "14") (pinfunction "C_14") (pintype "input"))
    )
    (net (code "94") (name "Net-(E8A-R{slash}C)") (class "Default")
      (node (ref "C63") (pin "1") (pinfunction "1_1") (pintype "passive"))
      (node (ref "E8") (pin "15") (pinfunction "R/C_15") (pintype "input"))
      (node (ref "R9") (pin "E") (pinfunction "E_E") (pintype "passive"))
      (node (ref "R9") (pin "S") (pinfunction "S_S") (pintype "passive"))
    )
    (net (code "95") (name "Net-(E8A-~{Q})") (class "Default")
      (node (ref "E8") (pin "10") (pinfunction "B_10") (pintype "input"))
      (node (ref "E8") (pin "4") (pinfunction "~{Q}_4") (pintype "output"))
    )
    (net (code "96") (name "Net-(E8B-C)") (class "Default")
      (node (ref "C62") (pin "2") (pinfunction "2_2") (pintype "passive"))
      (node (ref "E8") (pin "6") (pinfunction "C_6") (pintype "input"))
    )
    (net (code "97") (name "Net-(E8B-R{slash}C)") (class "Default")
      (node (ref "C62") (pin "1") (pinfunction "1_1") (pintype "passive"))
      (node (ref "E8") (pin "7") (pinfunction "R/C_7") (pintype "input"))
      (node (ref "R8") (pin "1") (pinfunction "1_1") (pintype "passive"))
    )
    (net (code "98") (name "Net-(E10A-I0)") (class "Default")
      (node (ref "E10") (pin "1") (pinfunction "I0_1") (pintype "input"))
      (node (ref "E10") (pin "2") (pinfunction "I1_2") (pintype "input"))
      (node (ref "E10") (pin "4") (pinfunction "I0_4") (pintype "input"))
      (node (ref "E10") (pin "5") (pinfunction "I1_5") (pintype "input"))
      (node (ref "E6") (pin "4") (pinfunction "O_4") (pintype "output"))
    )
    (net (code "99") (name "Net-(E10C-I1)") (class "Default")
      (node (ref "E10") (pin "10") (pinfunction "I1_10") (pintype "input"))
      (node (ref "E10") (pin "11") (pinfunction "O_11") (pintype "output"))
    )
    (net (code "100") (name "Net-(E10C-O)") (class "Default")
      (node (ref "E10") (pin "13") (pinfunction "I1_13") (pintype "input"))
      (node (ref "E10") (pin "8") (pinfunction "O_8") (pintype "output"))
      (node (ref "E11") (pin "12") (pinfunction "D_12") (pintype "input"))
      (node (ref "E11") (pin "13") (pinfunction "CLR_13") (pintype "input"))
    )
    (net (code "101") (name "Net-(E11A-CLK)") (class "Default")
      (node (ref "E11") (pin "3") (pinfunction "CLK_3") (pintype "input"))
      (node (ref "E11") (pin "9") (pinfunction "Q_9") (pintype "output"))
    )
    (net (code "102") (name "Net-(E12A-I)") (class "Default")
      (node (ref "D5") (pin "C") (pinfunction "C_C") (pintype "passive"))
      (node (ref "E12") (pin "1") (pinfunction "I_1") (pintype "input"))
      (node (ref "E13") (pin "5") (pinfunction "O_5") (pintype "open_collector"))
      (node (ref "R32") (pin "2") (pinfunction "2_2") (pintype "passive"))
    )
    (net (code "103") (name "Net-(E12A-O)") (class "Default")
      (node (ref "E12") (pin "2") (pinfunction "O_2") (pintype "output"))
      (node (ref "E15") (pin "2") (pinfunction "I1_2") (pintype "input"))
      (node (ref "E23") (pin "2") (pinfunction "I1_2") (pintype "input"))
    )
    (net (code "104") (name "Net-(E12B-O)") (class "Default")
      (node (ref "E12") (pin "4") (pinfunction "O_4") (pintype "output"))
      (node (ref "E13") (pin "6") (pinfunction "I0_6") (pintype "input"))
    )
    (net (code "105") (name "Net-(E12C-O)") (class "Default")
      (node (ref "E12") (pin "6") (pinfunction "O_6") (pintype "output"))
      (node (ref "E13") (pin "1") (pinfunction "I0_1") (pintype "input"))
    )
    (net (code "106") (name "Net-(E12D-O)") (class "Default")
      (node (ref "E12") (pin "8") (pinfunction "O_8") (pintype "output"))
      (node (ref "E18") (pin "10") (pinfunction "PRE_10") (pintype "input"))
      (node (ref "E18") (pin "11") (pinfunction "CLK_11") (pintype "input"))
      (node (ref "E18") (pin "12") (pinfunction "D_12") (pintype "input"))
      (node (ref "E18") (pin "13") (pinfunction "CLR_13") (pintype "input"))
    )
    (net (code "107") (name "Net-(E12E-I)") (class "Default")
      (node (ref "E12") (pin "11") (pinfunction "I_11") (pintype "input"))
      (node (ref "E23") (pin "12") (pinfunction "O_12") (pintype "output"))
      (node (ref "E23") (pin "9") (pinfunction "I0_9") (pintype "input"))
    )
    (net (code "108") (name "Net-(E12E-O)") (class "Default")
      (node (ref "E12") (pin "10") (pinfunction "O_10") (pintype "output"))
      (node (ref "E17") (pin "10") (pinfunction "I1_10") (pintype "input"))
      (node (ref "E17") (pin "12") (pinfunction "I0_12") (pintype "input"))
    )
    (net (code "109") (name "Net-(E12F-I)") (class "Default")
      (node (ref "C37") (pin "2") (pinfunction "2_2") (pintype "passive"))
      (node (ref "E12") (pin "13") (pinfunction "I_13") (pintype "input"))
      (node (ref "R22") (pin "1") (pinfunction "1_1") (pintype "passive"))
      (node (ref "R23") (pin "2") (pinfunction "2_2") (pintype "passive"))
    )
    (net (code "110") (name "Net-(E12F-O)") (class "Default")
      (node (ref "C37") (pin "1") (pinfunction "1_1") (pintype "passive"))
      (node (ref "E12") (pin "12") (pinfunction "O_12") (pintype "output"))
      (node (ref "E14") (pin "10") (pinfunction "B_10") (pintype "input"))
      (node (ref "E14") (pin "2") (pinfunction "B_2") (pintype "input"))
      (node (ref "E22") (pin "1") (pinfunction "I0_1") (pintype "input"))
    )
    (net (code "111") (name "Net-(E13A-O)") (class "Default")
      (node (ref "C36") (pin "1") (pinfunction "1_1") (pintype "passive"))
      (node (ref "E13") (pin "3") (pinfunction "O_3") (pintype "open_collector"))
      (node (ref "Q1") (pin "E") (pinfunction "E_E") (pintype "passive"))
      (node (ref "R20") (pin "1") (pinfunction "1_1") (pintype "passive"))
    )
    (net (code "112") (name "Net-(E13B-I1)") (class "Default")
      (node (ref "E13") (pin "7") (pinfunction "I1_7") (pintype "input"))
      (node (ref "E14") (pin "12") (pinfunction "~{Q}_12") (pintype "output"))
      (node (ref "E18") (pin "3") (pinfunction "CLK_3") (pintype "input"))
      (node (ref "E23") (pin "1") (pinfunction "I0_1") (pintype "input"))
    )
    (net (code "113") (name "Net-(E14A-C)") (class "Default")
      (node (ref "C35") (pin "2") (pinfunction "2_2") (pintype "passive"))
      (node (ref "E14") (pin "14") (pinfunction "C_14") (pintype "input"))
    )
    (net (code "114") (name "Net-(E14A-R{slash}C)") (class "Default")
      (node (ref "C35") (pin "1") (pinfunction "1_1") (pintype "passive"))
      (node (ref "E14") (pin "15") (pinfunction "R/C_15") (pintype "input"))
      (node (ref "R25") (pin "1") (pinfunction "1_1") (pintype "passive"))
    )
    (net (code "115") (name "Net-(E14A-~{Q})") (class "Default")
      (node (ref "E14") (pin "4") (pinfunction "~{Q}_4") (pintype "output"))
      (node (ref "E15") (pin "1") (pinfunction "I0_1") (pintype "input"))
    )
    (net (code "116") (name "Net-(E14B-C)") (class "Default")
      (node (ref "C25") (pin "2") (pinfunction "2_2") (pintype "passive"))
      (node (ref "E14") (pin "6") (pinfunction "C_6") (pintype "input"))
    )
    (net (code "117") (name "Net-(E14B-R{slash}C)") (class "Default")
      (node (ref "C25") (pin "1") (pinfunction "1_1") (pintype "passive"))
      (node (ref "E14") (pin "7") (pinfunction "R/C_7") (pintype "input"))
      (node (ref "R28") (pin "1") (pinfunction "1_1") (pintype "passive"))
    )
    (net (code "118") (name "Net-(E15A-O)") (class "Default")
      (node (ref "E15") (pin "3") (pinfunction "O_3") (pintype "output"))
      (node (ref "E16") (pin "11") (pinfunction "I2_11") (pintype "input"))
      (node (ref "E16") (pin "3") (pinfunction "I0_3") (pintype "input"))
    )
    (net (code "119") (name "Net-(E16A-I1)") (class "Default")
      (node (ref "E16") (pin "2") (pinfunction "I1_2") (pintype "input"))
      (node (ref "E17") (pin "11") (pinfunction "O_11") (pintype "output"))
    )
    (net (code "120") (name "Net-(E16A-O)") (class "Default")
      (node (ref "E16") (pin "12") (pinfunction "O_12") (pintype "output"))
      (node (ref "E19") (pin "14") (pinfunction "CLR_14") (pintype "input"))
      (node (ref "E20") (pin "14") (pinfunction "CLR_14") (pintype "input"))
    )
    (net (code "121") (name "Net-(E16B-O)") (class "Default")
      (node (ref "E16") (pin "6") (pinfunction "O_6") (pintype "output"))
      (node (ref "E19") (pin "5") (pinfunction "UP_5") (pintype "input"))
    )
    (net (code "122") (name "Net-(E16C-O)") (class "Default")
      (node (ref "E16") (pin "8") (pinfunction "O_8") (pintype "output"))
      (node (ref "E19") (pin "4") (pinfunction "DN_4") (pintype "input"))
    )
    (net (code "123") (name "Net-(E17A-I0)") (class "Default")
      (node (ref "E17") (pin "1") (pinfunction "I0_1") (pintype "input"))
      (node (ref "E17") (pin "6") (pinfunction "O_6") (pintype "output"))
    )
    (net (code "124") (name "Net-(E17A-O)") (class "Default")
      (node (ref "E17") (pin "3") (pinfunction "O_3") (pintype "output"))
      (node (ref "E17") (pin "4") (pinfunction "I0_4") (pintype "input"))
      (node (ref "E21") (pin "1") (pinfunction "I0_1") (pintype "input"))
    )
    (net (code "125") (name "Net-(E17C-O)") (class "Default")
      (node (ref "E17") (pin "8") (pinfunction "O_8") (pintype "output"))
      (node (ref "E19") (pin "11") (pinfunction "LD_11") (pintype "input"))
      (node (ref "E20") (pin "11") (pinfunction "LD_11") (pintype "input"))
    )
    (net (code "126") (name "Net-(E19A-BO)") (class "Default")
      (node (ref "E19") (pin "13") (pinfunction "BO_13") (pintype "output"))
      (node (ref "E20") (pin "4") (pinfunction "DN_4") (pintype "input"))
    )
    (net (code "127") (name "Net-(E19A-CO)") (class "Default")
      (node (ref "E19") (pin "12") (pinfunction "CO_12") (pintype "output"))
      (node (ref "E20") (pin "5") (pinfunction "UP_5") (pintype "input"))
    )
    (net (code "128") (name "Net-(E23A-I2)") (class "Default")
      (node (ref "E23") (pin "13") (pinfunction "I2_13") (pintype "input"))
      (node (ref "E23") (pin "8") (pinfunction "O_8") (pintype "output"))
    )
    (net (code "129") (name "Net-(E25-+IN)") (class "Default")
      (node (ref "E25") (pin "3") (pinfunction "+IN_3") (pintype "input"))
      (node (ref "R30") (pin "1") (pinfunction "1_1") (pintype "passive"))
      (node (ref "R31") (pin "2") (pinfunction "2_2") (pintype "passive"))
    )
    (net (code "130") (name "Net-(E25--IN)") (class "Default")
      (node (ref "C38") (pin "1") (pinfunction "1_1") (pintype "passive"))
      (node (ref "E25") (pin "2") (pinfunction "-IN_2") (pintype "input"))
      (node (ref "R29") (pin "1") (pinfunction "1_1") (pintype "passive"))
    )
    (net (code "131") (name "Net-(E25-OUT)") (class "Default")
      (node (ref "E25") (pin "6") (pinfunction "OUT_6") (pintype "output"))
      (node (ref "R29") (pin "2") (pinfunction "2_2") (pintype "passive"))
      (node (ref "R30") (pin "2") (pinfunction "2_2") (pintype "passive"))
      (node (ref "R32") (pin "1") (pinfunction "1_1") (pintype "passive"))
    )
    (net (code "132") (name "Net-(E26A-O)") (class "Default")
      (node (ref "E26") (pin "3") (pinfunction "O_3") (pintype "output"))
      (node (ref "E30") (pin "2") (pinfunction "I1_2") (pintype "input"))
    )
    (net (code "133") (name "Net-(E26B-O)") (class "Default")
      (node (ref "E26") (pin "6") (pinfunction "O_6") (pintype "output"))
      (node (ref "E30") (pin "7") (pinfunction "I1_7") (pintype "input"))
    )
    (net (code "134") (name "Net-(E26C-O)") (class "Default")
      (node (ref "E26") (pin "8") (pinfunction "O_8") (pintype "output"))
      (node (ref "E30") (pin "6") (pinfunction "I0_6") (pintype "input"))
    )
    (net (code "135") (name "Net-(E26D-O)") (class "Default")
      (node (ref "E26") (pin "11") (pinfunction "O_11") (pintype "output"))
      (node (ref "E30") (pin "1") (pinfunction "I0_1") (pintype "input"))
    )
    (net (code "136") (name "Net-(E27A-O)") (class "Default")
      (node (ref "E27") (pin "3") (pinfunction "O_3") (pintype "output"))
      (node (ref "E31") (pin "2") (pinfunction "I1_2") (pintype "input"))
    )
    (net (code "137") (name "Net-(E27B-O)") (class "Default")
      (node (ref "E27") (pin "6") (pinfunction "O_6") (pintype "output"))
      (node (ref "E31") (pin "7") (pinfunction "I1_7") (pintype "input"))
    )
    (net (code "138") (name "Net-(E27C-O)") (class "Default")
      (node (ref "E27") (pin "8") (pinfunction "O_8") (pintype "output"))
      (node (ref "E31") (pin "6") (pinfunction "I0_6") (pintype "input"))
    )
    (net (code "139") (name "Net-(E27D-O)") (class "Default")
      (node (ref "E27") (pin "11") (pinfunction "O_11") (pintype "output"))
      (node (ref "E31") (pin "1") (pinfunction "I0_1") (pintype "input"))
    )
    (net (code "140") (name "Net-(E28A-O)") (class "Default")
      (node (ref "E28") (pin "3") (pinfunction "O_3") (pintype "output"))
      (node (ref "E32") (pin "2") (pinfunction "I1_2") (pintype "input"))
    )
    (net (code "141") (name "Net-(E28B-O)") (class "Default")
      (node (ref "E28") (pin "6") (pinfunction "O_6") (pintype "output"))
      (node (ref "E32") (pin "7") (pinfunction "I1_7") (pintype "input"))
    )
    (net (code "142") (name "Net-(E28C-O)") (class "Default")
      (node (ref "E28") (pin "8") (pinfunction "O_8") (pintype "output"))
      (node (ref "E32") (pin "6") (pinfunction "I0_6") (pintype "input"))
    )
    (net (code "143") (name "Net-(E28D-O)") (class "Default")
      (node (ref "E28") (pin "11") (pinfunction "O_11") (pintype "output"))
      (node (ref "E32") (pin "1") (pinfunction "I0_1") (pintype "input"))
    )
    (net (code "144") (name "Net-(E29A-O)") (class "Default")
      (node (ref "E29") (pin "3") (pinfunction "O_3") (pintype "output"))
      (node (ref "E33") (pin "2") (pinfunction "I1_2") (pintype "input"))
    )
    (net (code "145") (name "Net-(E29B-O)") (class "Default")
      (node (ref "E29") (pin "6") (pinfunction "O_6") (pintype "output"))
      (node (ref "E33") (pin "7") (pinfunction "I1_7") (pintype "input"))
    )
    (net (code "146") (name "Net-(E29C-O)") (class "Default")
      (node (ref "E29") (pin "8") (pinfunction "O_8") (pintype "output"))
      (node (ref "E33") (pin "6") (pinfunction "I0_6") (pintype "input"))
    )
    (net (code "147") (name "Net-(E29D-O)") (class "Default")
      (node (ref "E29") (pin "11") (pinfunction "O_11") (pintype "output"))
      (node (ref "E33") (pin "1") (pinfunction "I0_1") (pintype "input"))
    )
    (net (code "148") (name "Net-(POWER_ON-PadA)") (class "Default")
      (node (ref "POWER_ON") (pin "A") (pinfunction "A_A") (pintype "passive"))
      (node (ref "R3") (pin "1") (pinfunction "1_1") (pintype "passive"))
    )
    (net (code "149") (name "Net-(Q1-PadB1)") (class "Default")
      (node (ref "Q1") (pin "B1") (pinfunction "B1_B1") (pintype "passive"))
      (node (ref "R21") (pin "1") (pinfunction "1_1") (pintype "passive"))
    )
    (net (code "150") (name "Net-(Q1-PadB2)") (class "Default")
      (node (ref "Q1") (pin "B2") (pinfunction "B2_B2") (pintype "passive"))
      (node (ref "R22") (pin "2") (pinfunction "2_2") (pintype "passive"))
    )
    (net (code "151") (name "Net-(R2-Pad1)") (class "Default")
      (node (ref "R2") (pin "1") (pinfunction "1_1") (pintype "passive"))
      (node (ref "SEEK_INC") (pin "A") (pinfunction "A_A") (pintype "passive"))
    )
    (net (code "152") (name "Net-(RTZ-O)") (class "Default")
      (node (ref "RTZ") (pin "1") (pinfunction "O_1") (pintype "passive"))
      (node (ref "RUN") (pin "2") (pinfunction "P_2") (pintype "passive"))
    )
    (net (code "153") (name "OSC_L") (class "Default")
      (node (ref "E16") (pin "13") (pinfunction "I2_13") (pintype "input"))
      (node (ref "FUNCTION") (pin "3") (pinfunction "A3_3") (pintype "passive"))
      (node (ref "R35") (pin "1") (pinfunction "1_1") (pintype "passive"))
    )
    (net (code "154") (name "RANDOM_L") (class "Default")
      (node (ref "D1") (pin "C") (pinfunction "C_C") (pintype "passive"))
      (node (ref "E12") (pin "3") (pinfunction "I_3") (pintype "input"))
      (node (ref "FUNCTION") (pin "4") (pinfunction "A4_4") (pintype "passive"))
      (node (ref "R34") (pin "1") (pinfunction "1_1") (pintype "passive"))
    )
    (net (code "155") (name "READ_CLOCK") (class "Default")
      (node (ref "J1") (pin "F") (pinfunction "P$2_F") (pintype "bidirectional"))
      (node (ref "RN1") (pin "3") (pinfunction "2_3") (pintype "passive"))
      (node (ref "RN5") (pin "3") (pinfunction "2_3") (pintype "passive"))
    )
    (net (code "156") (name "READ_DATA") (class "Default")
      (node (ref "J1") (pin "D") (pinfunction "P$2_D") (pintype "bidirectional"))
      (node (ref "RN1") (pin "2") (pinfunction "2_2") (pintype "passive"))
      (node (ref "RN5") (pin "2") (pinfunction "2_2") (pintype "passive"))
    )
    (net (code "157") (name "REV_L") (class "Default")
      (node (ref "E16") (pin "5") (pinfunction "I2_5") (pintype "input"))
      (node (ref "E17") (pin "13") (pinfunction "I1_13") (pintype "input"))
      (node (ref "FWD/REV") (pin "1") (pinfunction "O_1") (pintype "passive"))
      (node (ref "R33") (pin "1") (pinfunction "1_1") (pintype "passive"))
    )
    (net (code "158") (name "RK05_AU2") (class "Default")
      (node (ref "J2") (pin "A") (pinfunction "P$2_A") (pintype "bidirectional"))
      (node (ref "RN3") (pin "2") (pinfunction "2_2") (pintype "passive"))
      (node (ref "RN7") (pin "2") (pinfunction "2_2") (pintype "passive"))
    )
    (net (code "159") (name "RK05_BH2") (class "Default")
      (node (ref "J1") (pin "NN") (pinfunction "P$2_NN") (pintype "bidirectional"))
      (node (ref "RN2") (pin "4") (pinfunction "2_4") (pintype "passive"))
      (node (ref "RN6") (pin "4") (pinfunction "2_4") (pintype "passive"))
    )
    (net (code "160") (name "RTZ_L") (class "Default")
      (node (ref "E16") (pin "1") (pinfunction "I0_1") (pintype "input"))
      (node (ref "E17") (pin "2") (pinfunction "I1_2") (pintype "input"))
      (node (ref "E22") (pin "7") (pinfunction "I1_7") (pintype "input"))
      (node (ref "R24") (pin "1") (pinfunction "1_1") (pintype "passive"))
      (node (ref "RTZ") (pin "3") (pinfunction "S_3") (pintype "passive"))
    )
    (net (code "161") (name "RUN_L") (class "Default")
      (node (ref "E13") (pin "2") (pinfunction "I1_2") (pintype "input"))
      (node (ref "R19") (pin "1") (pinfunction "1_1") (pintype "passive"))
      (node (ref "RUN") (pin "1") (pinfunction "O_1") (pintype "passive"))
    )
    (net (code "162") (name "SECTOR_0L") (class "Default")
      (node (ref "E3") (pin "1") (pinfunction "O0_1") (pintype "output"))
      (node (ref "SECTOR") (pin "1") (pinfunction "1_1") (pintype "passive"))
    )
    (net (code "163") (name "SECTOR_1L") (class "Default")
      (node (ref "E3") (pin "2") (pinfunction "O1_2") (pintype "output"))
      (node (ref "SECTOR") (pin "2") (pinfunction "2_2") (pintype "passive"))
    )
    (net (code "164") (name "SECTOR_2L") (class "Default")
      (node (ref "E3") (pin "3") (pinfunction "O2_3") (pintype "output"))
      (node (ref "SECTOR") (pin "3") (pinfunction "3_3") (pintype "passive"))
    )
    (net (code "165") (name "SECTOR_3L") (class "Default")
      (node (ref "E3") (pin "4") (pinfunction "O3_4") (pintype "output"))
      (node (ref "SECTOR") (pin "4") (pinfunction "4_4") (pintype "passive"))
    )
    (net (code "166") (name "SECTOR_4L") (class "Default")
      (node (ref "E3") (pin "5") (pinfunction "O4_5") (pintype "output"))
      (node (ref "SECTOR") (pin "5") (pinfunction "5_5") (pintype "passive"))
    )
    (net (code "167") (name "SECTOR_5L") (class "Default")
      (node (ref "E3") (pin "6") (pinfunction "O5_6") (pintype "output"))
      (node (ref "SECTOR") (pin "6") (pinfunction "6_6") (pintype "passive"))
    )
    (net (code "168") (name "SECTOR_6L") (class "Default")
      (node (ref "E3") (pin "7") (pinfunction "O6_7") (pintype "output"))
      (node (ref "SECTOR") (pin "7") (pinfunction "7_7") (pintype "passive"))
    )
    (net (code "169") (name "SECTOR_7L") (class "Default")
      (node (ref "E3") (pin "9") (pinfunction "O7_9") (pintype "output"))
      (node (ref "SECTOR") (pin "8") (pinfunction "8_8") (pintype "passive"))
    )
    (net (code "170") (name "SECTOR_8L") (class "Default")
      (node (ref "E3") (pin "10") (pinfunction "O8_10") (pintype "output"))
      (node (ref "SECTOR") (pin "9") (pinfunction "9_9") (pintype "passive"))
    )
    (net (code "171") (name "SECTOR_9L") (class "Default")
      (node (ref "E3") (pin "11") (pinfunction "O9_11") (pintype "output"))
      (node (ref "SECTOR") (pin "10") (pinfunction "10_10") (pintype "passive"))
    )
    (net (code "172") (name "SECTOR_SELECT_L") (class "Default")
      (node (ref "E7") (pin "1") (pinfunction "I0_1") (pintype "input"))
      (node (ref "SECTOR") (pin "C") (pinfunction "A_C") (pintype "passive"))
    )
    (net (code "173") (name "SEEK_INCOMPLETE_L") (class "Default")
      (node (ref "E21") (pin "3") (pinfunction "O_3") (pintype "open_collector"))
      (node (ref "SEEK_INC") (pin "B") (pinfunction "B_B") (pintype "passive"))
    )
    (net (code "174") (name "SELECT_0L") (class "Default")
      (node (ref "DRIVE") (pin "1") (pinfunction "A1_1") (pintype "passive"))
      (node (ref "J2") (pin "AA") (pinfunction "P$2_AA") (pintype "bidirectional"))
      (node (ref "RN4") (pin "10") (pinfunction "2_10") (pintype "passive"))
      (node (ref "RN8") (pin "10") (pinfunction "2_10") (pintype "passive"))
    )
    (net (code "175") (name "SELECT_1L") (class "Default")
      (node (ref "DRIVE") (pin "2") (pinfunction "A2_2") (pintype "passive"))
      (node (ref "J2") (pin "W") (pinfunction "P$2_W") (pintype "bidirectional"))
      (node (ref "R69") (pin "1") (pinfunction "1_1") (pintype "passive"))
      (node (ref "R70") (pin "2") (pinfunction "2_2") (pintype "passive"))
    )
    (net (code "176") (name "SELECT_2L") (class "Default")
      (node (ref "DRIVE") (pin "3") (pinfunction "A3_3") (pintype "passive"))
      (node (ref "J2") (pin "S") (pinfunction "P$2_S") (pintype "bidirectional"))
      (node (ref "RN3") (pin "9") (pinfunction "2_9") (pintype "passive"))
      (node (ref "RN7") (pin "9") (pinfunction "2_9") (pintype "passive"))
    )
    (net (code "177") (name "SELECT_3L") (class "Default")
      (node (ref "DRIVE") (pin "4") (pinfunction "A4_4") (pintype "passive"))
      (node (ref "J2") (pin "M") (pinfunction "P$2_M") (pintype "bidirectional"))
      (node (ref "RN3") (pin "7") (pinfunction "2_7") (pintype "passive"))
      (node (ref "RN7") (pin "7") (pinfunction "2_7") (pintype "passive"))
    )
    (net (code "178") (name "STEP_L") (class "Default")
      (node (ref "D1") (pin "A") (pinfunction "A_A") (pintype "passive"))
      (node (ref "E18") (pin "1") (pinfunction "CLR_1") (pintype "input"))
      (node (ref "FUNCTION") (pin "1") (pinfunction "A1_1") (pintype "passive"))
      (node (ref "R37") (pin "1") (pinfunction "1_1") (pintype "passive"))
    )
    (net (code "179") (name "VCC") (class "Default")
      (node (ref "C1") (pin "1") (pinfunction "1_1") (pintype "passive"))
      (node (ref "C10") (pin "1") (pinfunction "1_1") (pintype "passive"))
      (node (ref "C11") (pin "1") (pinfunction "1_1") (pintype "passive"))
      (node (ref "C12") (pin "1") (pinfunction "1_1") (pintype "passive"))
      (node (ref "C13") (pin "1") (pinfunction "1_1") (pintype "passive"))
      (node (ref "C14") (pin "1") (pinfunction "1_1") (pintype "passive"))
      (node (ref "C15") (pin "1") (pinfunction "1_1") (pintype "passive"))
      (node (ref "C16") (pin "1") (pinfunction "1_1") (pintype "passive"))
      (node (ref "C17") (pin "1") (pinfunction "1_1") (pintype "passive"))
      (node (ref "C18") (pin "1") (pinfunction "1_1") (pintype "passive"))
      (node (ref "C19") (pin "1") (pinfunction "1_1") (pintype "passive"))
      (node (ref "C2") (pin "1") (pinfunction "1_1") (pintype "passive"))
      (node (ref "C20") (pin "1") (pinfunction "1_1") (pintype "passive"))
      (node (ref "C21") (pin "1") (pinfunction "1_1") (pintype "passive"))
      (node (ref "C22") (pin "1") (pinfunction "1_1") (pintype "passive"))
      (node (ref "C23") (pin "1") (pinfunction "1_1") (pintype "passive"))
      (node (ref "C24") (pin "1") (pinfunction "1_1") (pintype "passive"))
      (node (ref "C26") (pin "1") (pinfunction "1_1") (pintype "passive"))
      (node (ref "C27") (pin "1") (pinfunction "1_1") (pintype "passive"))
      (node (ref "C28") (pin "1") (pinfunction "1_1") (pintype "passive"))
      (node (ref "C29") (pin "1") (pinfunction "1_1") (pintype "passive"))
      (node (ref "C3") (pin "1") (pinfunction "1_1") (pintype "passive"))
      (node (ref "C30") (pin "1") (pinfunction "1_1") (pintype "passive"))
      (node (ref "C31") (pin "1") (pinfunction "1_1") (pintype "passive"))
      (node (ref "C32") (pin "1") (pinfunction "1_1") (pintype "passive"))
      (node (ref "C33") (pin "1") (pinfunction "1_1") (pintype "passive"))
      (node (ref "C4") (pin "1") (pinfunction "1_1") (pintype "passive"))
      (node (ref "C40") (pin "1") (pinfunction "1_1") (pintype "passive"))
      (node (ref "C41") (pin "1") (pinfunction "1_1") (pintype "passive"))
      (node (ref "C42") (pin "1") (pinfunction "1_1") (pintype "passive"))
      (node (ref "C43") (pin "1") (pinfunction "1_1") (pintype "passive"))
      (node (ref "C5") (pin "1") (pinfunction "1_1") (pintype "passive"))
      (node (ref "C52") (pin "+") (pinfunction "+_+") (pintype "passive"))
      (node (ref "C6") (pin "1") (pinfunction "1_1") (pintype "passive"))
      (node (ref "C60") (pin "+") (pinfunction "+_+") (pintype "passive"))
      (node (ref "C61") (pin "+") (pinfunction "+_+") (pintype "passive"))
      (node (ref "C67") (pin "+") (pinfunction "+_+") (pintype "passive"))
      (node (ref "C68") (pin "+") (pinfunction "+_+") (pintype "passive"))
      (node (ref "C7") (pin "1") (pinfunction "1_1") (pintype "passive"))
      (node (ref "C8") (pin "1") (pinfunction "1_1") (pintype "passive"))
      (node (ref "C9") (pin "1") (pinfunction "1_1") (pintype "passive"))
      (node (ref "D2") (pin "A") (pinfunction "A_A") (pintype "passive"))
      (node (ref "E5") (pin "1") (pinfunction "CLR_1") (pintype "input"))
      (node (ref "E5") (pin "4") (pinfunction "PRE_4") (pintype "input"))
      (node (ref "POWER") (pin "2") (pinfunction "2_2") (pintype "passive"))
      (node (ref "R10") (pin "2") (pinfunction "2_2") (pintype "passive"))
      (node (ref "R11") (pin "2") (pinfunction "2_2") (pintype "passive"))
      (node (ref "R12") (pin "2") (pinfunction "2_2") (pintype "passive"))
      (node (ref "R13") (pin "2") (pinfunction "2_2") (pintype "passive"))
      (node (ref "R147") (pin "2") (pinfunction "2_2") (pintype "passive"))
      (node (ref "R16") (pin "2") (pinfunction "2_2") (pintype "passive"))
      (node (ref "R17") (pin "2") (pinfunction "2_2") (pintype "passive"))
      (node (ref "R18") (pin "2") (pinfunction "2_2") (pintype "passive"))
      (node (ref "R19") (pin "2") (pinfunction "2_2") (pintype "passive"))
      (node (ref "R24") (pin "2") (pinfunction "2_2") (pintype "passive"))
      (node (ref "R25") (pin "2") (pinfunction "2_2") (pintype "passive"))
      (node (ref "R26") (pin "2") (pinfunction "2_2") (pintype "passive"))
      (node (ref "R27") (pin "2") (pinfunction "2_2") (pintype "passive"))
      (node (ref "R28") (pin "2") (pinfunction "2_2") (pintype "passive"))
      (node (ref "R33") (pin "2") (pinfunction "2_2") (pintype "passive"))
      (node (ref "R34") (pin "2") (pinfunction "2_2") (pintype "passive"))
      (node (ref "R35") (pin "2") (pinfunction "2_2") (pintype "passive"))
      (node (ref "R36") (pin "2") (pinfunction "2_2") (pintype "passive"))
      (node (ref "R37") (pin "2") (pinfunction "2_2") (pintype "passive"))
      (node (ref "R38") (pin "1") (pinfunction "1_1") (pintype "passive"))
      (node (ref "R39") (pin "1") (pinfunction "1_1") (pintype "passive"))
      (node (ref "R4") (pin "2") (pinfunction "2_2") (pintype "passive"))
      (node (ref "R40") (pin "1") (pinfunction "1_1") (pintype "passive"))
      (node (ref "R41") (pin "1") (pinfunction "1_1") (pintype "passive"))
      (node (ref "R42") (pin "1") (pinfunction "1_1") (pintype "passive"))
      (node (ref "R43") (pin "1") (pinfunction "1_1") (pintype "passive"))
      (node (ref "R44") (pin "1") (pinfunction "1_1") (pintype "passive"))
      (node (ref "R45") (pin "1") (pinfunction "1_1") (pintype "passive"))
      (node (ref "R46") (pin "2") (pinfunction "2_2") (pintype "passive"))
      (node (ref "R5") (pin "2") (pinfunction "2_2") (pintype "passive"))
      (node (ref "R50") (pin "2") (pinfunction "2_2") (pintype "passive"))
      (node (ref "R6") (pin "2") (pinfunction "2_2") (pintype "passive"))
      (node (ref "R69") (pin "2") (pinfunction "2_2") (pintype "passive"))
      (node (ref "R7") (pin "2") (pinfunction "2_2") (pintype "passive"))
      (node (ref "R8") (pin "2") (pinfunction "2_2") (pintype "passive"))
      (node (ref "R9") (pin "A") (pinfunction "A_A") (pintype "passive"))
      (node (ref "RN1") (pin "1") (pinfunction "1_1") (pintype "passive"))
      (node (ref "RN2") (pin "1") (pinfunction "1_1") (pintype "passive"))
      (node (ref "RN2") (pin "2") (pinfunction "2_2") (pintype "passive"))
      (node (ref "RN3") (pin "1") (pinfunction "1_1") (pintype "passive"))
      (node (ref "RN4") (pin "1") (pinfunction "1_1") (pintype "passive"))
    )
    (net (code "180") (name "WRITE_GATE") (class "Default")
      (node (ref "E11") (pin "5") (pinfunction "Q_5") (pintype "output"))
      (node (ref "E2") (pin "1") (pinfunction "CLR_1") (pintype "input"))
      (node (ref "E2") (pin "13") (pinfunction "CLR_13") (pintype "input"))
      (node (ref "E5") (pin "13") (pinfunction "CLR_13") (pintype "input"))
      (node (ref "E8") (pin "11") (pinfunction "CLR_11") (pintype "input"))
      (node (ref "E8") (pin "2") (pinfunction "B_2") (pintype "input"))
      (node (ref "E8") (pin "3") (pinfunction "CLR_3") (pintype "input"))
      (node (ref "E9") (pin "11") (pinfunction "I0_11") (pintype "input"))
    )
    (net (code "181") (name "WRITE_H") (class "Default")
      (node (ref "E10") (pin "12") (pinfunction "I0_12") (pintype "input"))
      (node (ref "R5") (pin "1") (pinfunction "1_1") (pintype "passive"))
      (node (ref "WRITE_BUTTON") (pin "1") (pinfunction "O_1") (pintype "passive"))
    )
    (net (code "182") (name "WRITE_L") (class "Default")
      (node (ref "E10") (pin "9") (pinfunction "I0_9") (pintype "input"))
      (node (ref "R6") (pin "1") (pinfunction "1_1") (pintype "passive"))
      (node (ref "WRITE_BUTTON") (pin "3") (pinfunction "S_3") (pintype "passive"))
    )
    (net (code "183") (name "unconnected-(CYL1-O-Pad1)") (class "Default")
      (node (ref "CYL1") (pin "1") (pinfunction "O_1") (pintype "passive"))
    )
    (net (code "184") (name "unconnected-(CYL2-O-Pad1)") (class "Default")
      (node (ref "CYL2") (pin "1") (pinfunction "O_1") (pintype "passive"))
    )
    (net (code "185") (name "unconnected-(CYL4-O-Pad1)") (class "Default")
      (node (ref "CYL4") (pin "1") (pinfunction "O_1") (pintype "passive"))
    )
    (net (code "186") (name "unconnected-(CYL8-O-Pad1)") (class "Default")
      (node (ref "CYL8") (pin "1") (pinfunction "O_1") (pintype "passive"))
    )
    (net (code "187") (name "unconnected-(CYL16-O-Pad1)") (class "Default")
      (node (ref "CYL16") (pin "1") (pinfunction "O_1") (pintype "passive"))
    )
    (net (code "188") (name "unconnected-(CYL32-O-Pad1)") (class "Default")
      (node (ref "CYL32") (pin "1") (pinfunction "O_1") (pintype "passive"))
    )
    (net (code "189") (name "unconnected-(CYL64-O-Pad1)") (class "Default")
      (node (ref "CYL64") (pin "1") (pinfunction "O_1") (pintype "passive"))
    )
    (net (code "190") (name "unconnected-(CYL128-O-Pad1)") (class "Default")
      (node (ref "CYL128") (pin "1") (pinfunction "O_1") (pintype "passive"))
    )
    (net (code "191") (name "unconnected-(DRIVE-B-PadC2)") (class "Default")
      (node (ref "DRIVE") (pin "C2") (pinfunction "B_C2") (pintype "passive"))
    )
    (net (code "192") (name "unconnected-(DRIVE-B1-Pad5)") (class "Default")
      (node (ref "DRIVE") (pin "5") (pinfunction "B1_5") (pintype "passive"))
    )
    (net (code "193") (name "unconnected-(DRIVE-B2-Pad6)") (class "Default")
      (node (ref "DRIVE") (pin "6") (pinfunction "B2_6") (pintype "passive"))
    )
    (net (code "194") (name "unconnected-(DRIVE-B3-Pad7)") (class "Default")
      (node (ref "DRIVE") (pin "7") (pinfunction "B3_7") (pintype "passive"))
    )
    (net (code "195") (name "unconnected-(DRIVE-B4-Pad8)") (class "Default")
      (node (ref "DRIVE") (pin "8") (pinfunction "B4_8") (pintype "passive"))
    )
    (net (code "196") (name "unconnected-(DRIVE-C-PadC3)") (class "Default")
      (node (ref "DRIVE") (pin "C3") (pinfunction "C_C3") (pintype "passive"))
    )
    (net (code "197") (name "unconnected-(DRIVE-C1-Pad9)") (class "Default")
      (node (ref "DRIVE") (pin "9") (pinfunction "C1_9") (pintype "passive"))
    )
    (net (code "198") (name "unconnected-(DRIVE-C2-Pad10)") (class "Default")
      (node (ref "DRIVE") (pin "10") (pinfunction "C2_10") (pintype "passive"))
    )
    (net (code "199") (name "unconnected-(DRIVE-C3-Pad11)") (class "Default")
      (node (ref "DRIVE") (pin "11") (pinfunction "C3_11") (pintype "passive"))
    )
    (net (code "200") (name "unconnected-(DRIVE-C4-Pad12)") (class "Default")
      (node (ref "DRIVE") (pin "12") (pinfunction "C4_12") (pintype "passive"))
    )
    (net (code "201") (name "unconnected-(E5A-Q-Pad5)") (class "Default")
      (node (ref "E5") (pin "5") (pinfunction "Q_5") (pintype "output"))
    )
    (net (code "202") (name "unconnected-(E5A-~{Q}-Pad6)") (class "Default")
      (node (ref "E5") (pin "6") (pinfunction "~{Q}_6") (pintype "output"))
    )
    (net (code "203") (name "unconnected-(E5B-Q-Pad9)") (class "Default")
      (node (ref "E5") (pin "9") (pinfunction "Q_9") (pintype "output"))
    )
    (net (code "204") (name "unconnected-(E8A-Q-Pad13)") (class "Default")
      (node (ref "E8") (pin "13") (pinfunction "Q_13") (pintype "output"))
    )
    (net (code "205") (name "unconnected-(E9A-O-Pad1)") (class "Default")
      (node (ref "E9") (pin "1") (pinfunction "O_1") (pintype "open_collector"))
    )
    (net (code "206") (name "unconnected-(E9B-O-Pad4)") (class "Default")
      (node (ref "E9") (pin "4") (pinfunction "O_4") (pintype "open_collector"))
    )
    (net (code "207") (name "unconnected-(E10A-O-Pad3)") (class "Default")
      (node (ref "E10") (pin "3") (pinfunction "O_3") (pintype "output"))
    )
    (net (code "208") (name "unconnected-(E10B-O-Pad6)") (class "Default")
      (node (ref "E10") (pin "6") (pinfunction "O_6") (pintype "output"))
    )
    (net (code "209") (name "unconnected-(E11A-~{Q}-Pad6)") (class "Default")
      (node (ref "E11") (pin "6") (pinfunction "~{Q}_6") (pintype "output"))
    )
    (net (code "210") (name "unconnected-(E11B-~{Q}-Pad8)") (class "Default")
      (node (ref "E11") (pin "8") (pinfunction "~{Q}_8") (pintype "output"))
    )
    (net (code "211") (name "unconnected-(E14A-Q-Pad13)") (class "Default")
      (node (ref "E14") (pin "13") (pinfunction "Q_13") (pintype "output"))
    )
    (net (code "212") (name "unconnected-(E14B-Q-Pad5)") (class "Default")
      (node (ref "E14") (pin "5") (pinfunction "Q_5") (pintype "output"))
    )
    (net (code "213") (name "unconnected-(E15B-O-Pad6)") (class "Default")
      (node (ref "E15") (pin "6") (pinfunction "O_6") (pintype "output"))
    )
    (net (code "214") (name "unconnected-(E15C-O-Pad8)") (class "Default")
      (node (ref "E15") (pin "8") (pinfunction "O_8") (pintype "output"))
    )
    (net (code "215") (name "unconnected-(E15D-O-Pad11)") (class "Default")
      (node (ref "E15") (pin "11") (pinfunction "O_11") (pintype "output"))
    )
    (net (code "216") (name "unconnected-(E18B-Q-Pad9)") (class "Default")
      (node (ref "E18") (pin "9") (pinfunction "Q_9") (pintype "output"))
    )
    (net (code "217") (name "unconnected-(E18B-~{Q}-Pad8)") (class "Default")
      (node (ref "E18") (pin "8") (pinfunction "~{Q}_8") (pintype "output"))
    )
    (net (code "218") (name "unconnected-(E20A-BO-Pad13)") (class "Default")
      (node (ref "E20") (pin "13") (pinfunction "BO_13") (pintype "output"))
    )
    (net (code "219") (name "unconnected-(E20A-CO-Pad12)") (class "Default")
      (node (ref "E20") (pin "12") (pinfunction "CO_12") (pintype "output"))
    )
    (net (code "220") (name "unconnected-(E24B-O-Pad8)") (class "Default")
      (node (ref "E24") (pin "8") (pinfunction "O_8") (pintype "output"))
    )
    (net (code "221") (name "unconnected-(E25-ON1-Pad1)") (class "Default")
      (node (ref "E25") (pin "1") (pinfunction "ON1_1") (pintype "passive"))
    )
    (net (code "222") (name "unconnected-(E25-ON2-Pad5)") (class "Default")
      (node (ref "E25") (pin "5") (pinfunction "ON2_5") (pintype "passive"))
    )
    (net (code "223") (name "unconnected-(E25-OPT-Pad8)") (class "Default")
      (node (ref "E25") (pin "8") (pinfunction "OPT_8") (pintype "passive"))
    )
    (net (code "224") (name "unconnected-(FUNCTION-A2-Pad2)") (class "Default")
      (node (ref "FUNCTION") (pin "2") (pinfunction "A2_2") (pintype "passive"))
    )
    (net (code "225") (name "unconnected-(FUNCTION-B-PadC2)") (class "Default")
      (node (ref "FUNCTION") (pin "C2") (pinfunction "B_C2") (pintype "passive"))
    )
    (net (code "226") (name "unconnected-(FUNCTION-B1-Pad5)") (class "Default")
      (node (ref "FUNCTION") (pin "5") (pinfunction "B1_5") (pintype "passive"))
    )
    (net (code "227") (name "unconnected-(FUNCTION-B2-Pad6)") (class "Default")
      (node (ref "FUNCTION") (pin "6") (pinfunction "B2_6") (pintype "passive"))
    )
    (net (code "228") (name "unconnected-(FUNCTION-B3-Pad7)") (class "Default")
      (node (ref "FUNCTION") (pin "7") (pinfunction "B3_7") (pintype "passive"))
    )
    (net (code "229") (name "unconnected-(FUNCTION-B4-Pad8)") (class "Default")
      (node (ref "FUNCTION") (pin "8") (pinfunction "B4_8") (pintype "passive"))
    )
    (net (code "230") (name "unconnected-(FUNCTION-C-PadC3)") (class "Default")
      (node (ref "FUNCTION") (pin "C3") (pinfunction "C_C3") (pintype "passive"))
    )
    (net (code "231") (name "unconnected-(FUNCTION-C1-Pad9)") (class "Default")
      (node (ref "FUNCTION") (pin "9") (pinfunction "C1_9") (pintype "passive"))
    )
    (net (code "232") (name "unconnected-(FUNCTION-C2-Pad10)") (class "Default")
      (node (ref "FUNCTION") (pin "10") (pinfunction "C2_10") (pintype "passive"))
    )
    (net (code "233") (name "unconnected-(FUNCTION-C3-Pad11)") (class "Default")
      (node (ref "FUNCTION") (pin "11") (pinfunction "C3_11") (pintype "passive"))
    )
    (net (code "234") (name "unconnected-(FUNCTION-C4-Pad12)") (class "Default")
      (node (ref "FUNCTION") (pin "12") (pinfunction "C4_12") (pintype "passive"))
    )
    (net (code "235") (name "unconnected-(HEAD-O-Pad1)") (class "Default")
      (node (ref "HEAD") (pin "1") (pinfunction "O_1") (pintype "passive"))
    )
    (net (code "236") (name "unconnected-(RUN-S-Pad3)") (class "Default")
      (node (ref "RUN") (pin "3") (pinfunction "S_3") (pintype "passive"))
    )
  )
)
